# transponder-10_0_1.net
KiCad netlist of a schematic drawn in EAGLE
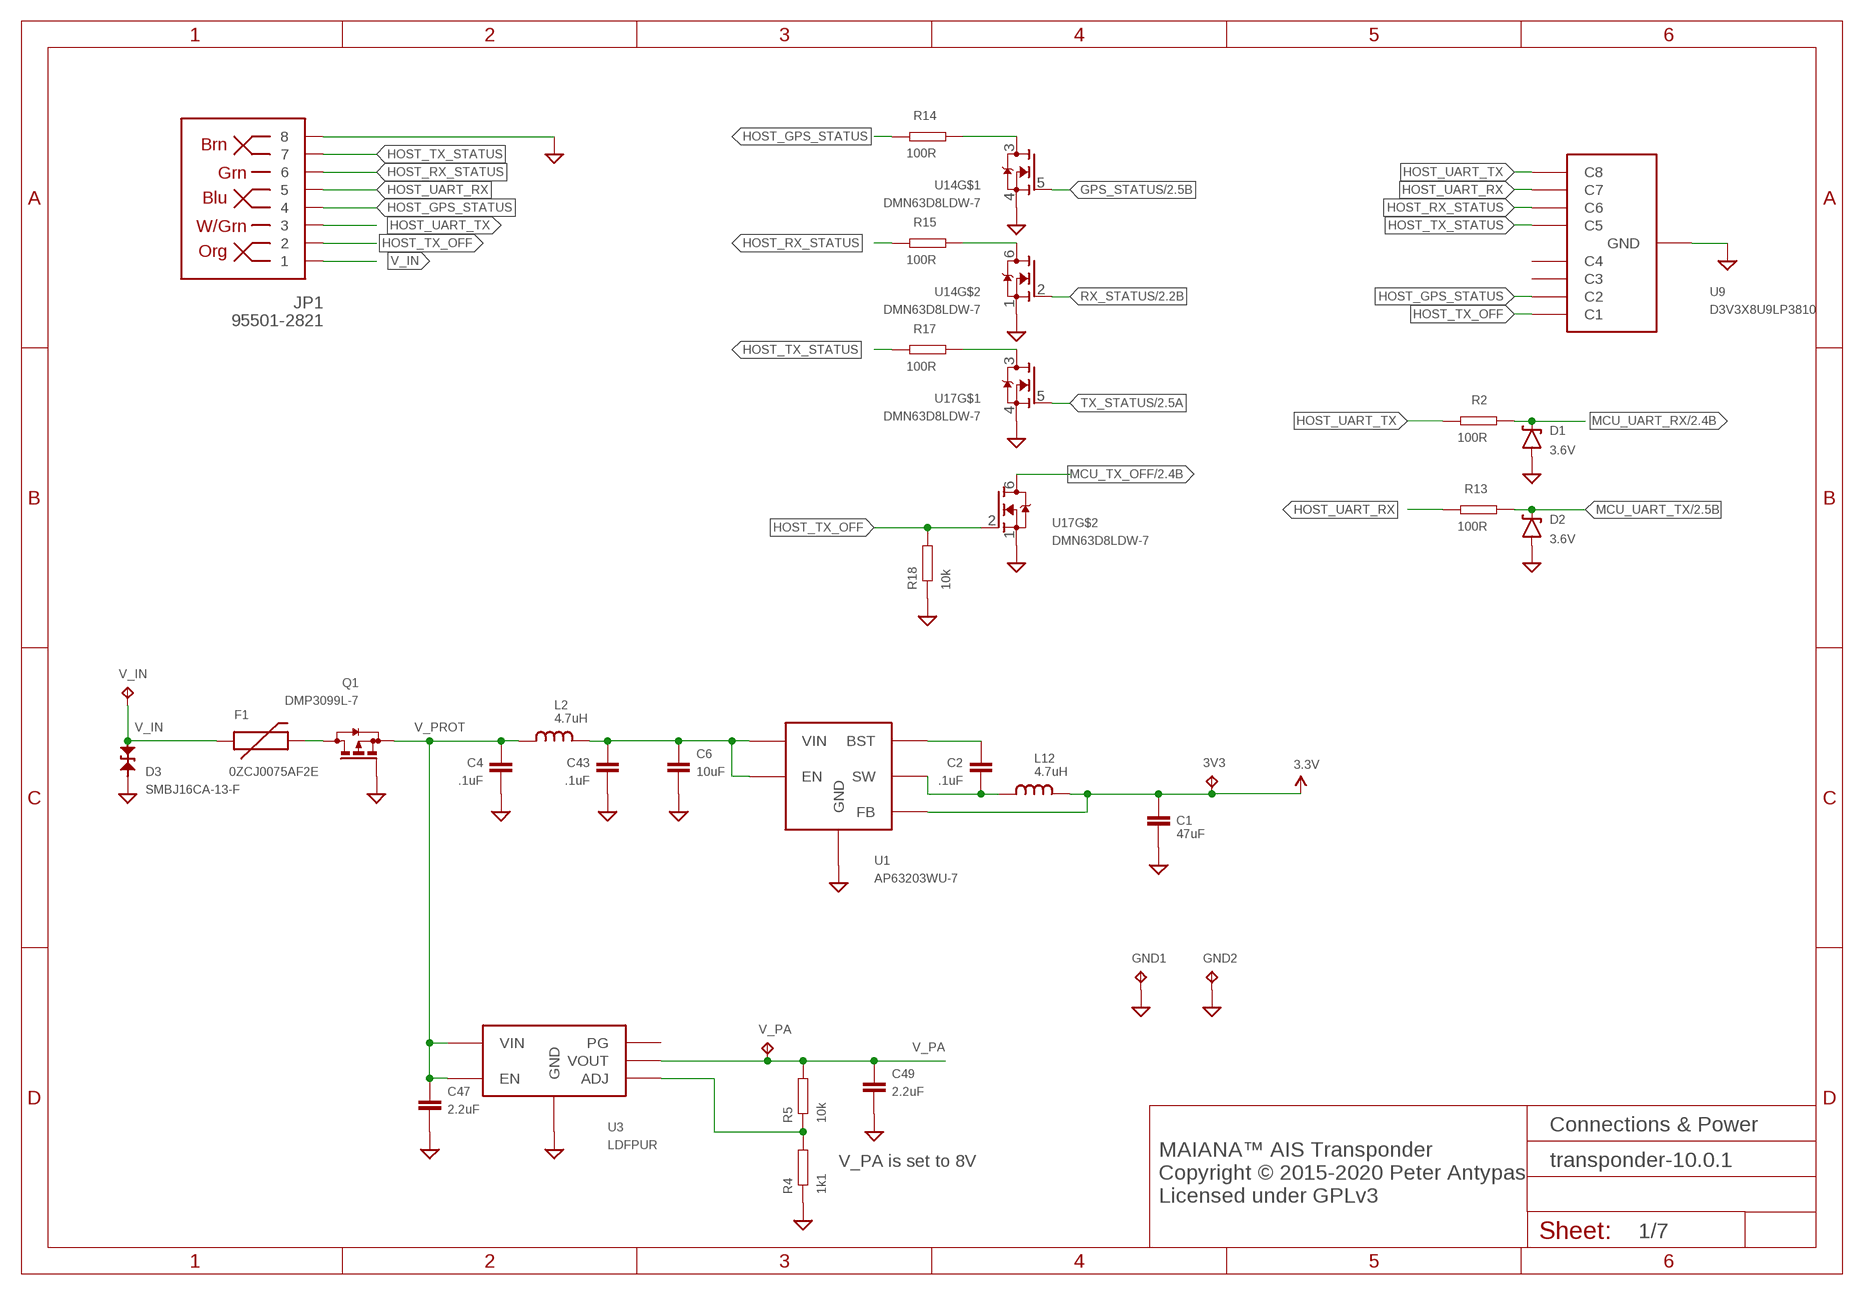
[diagram p0: schematic, sheet 1]
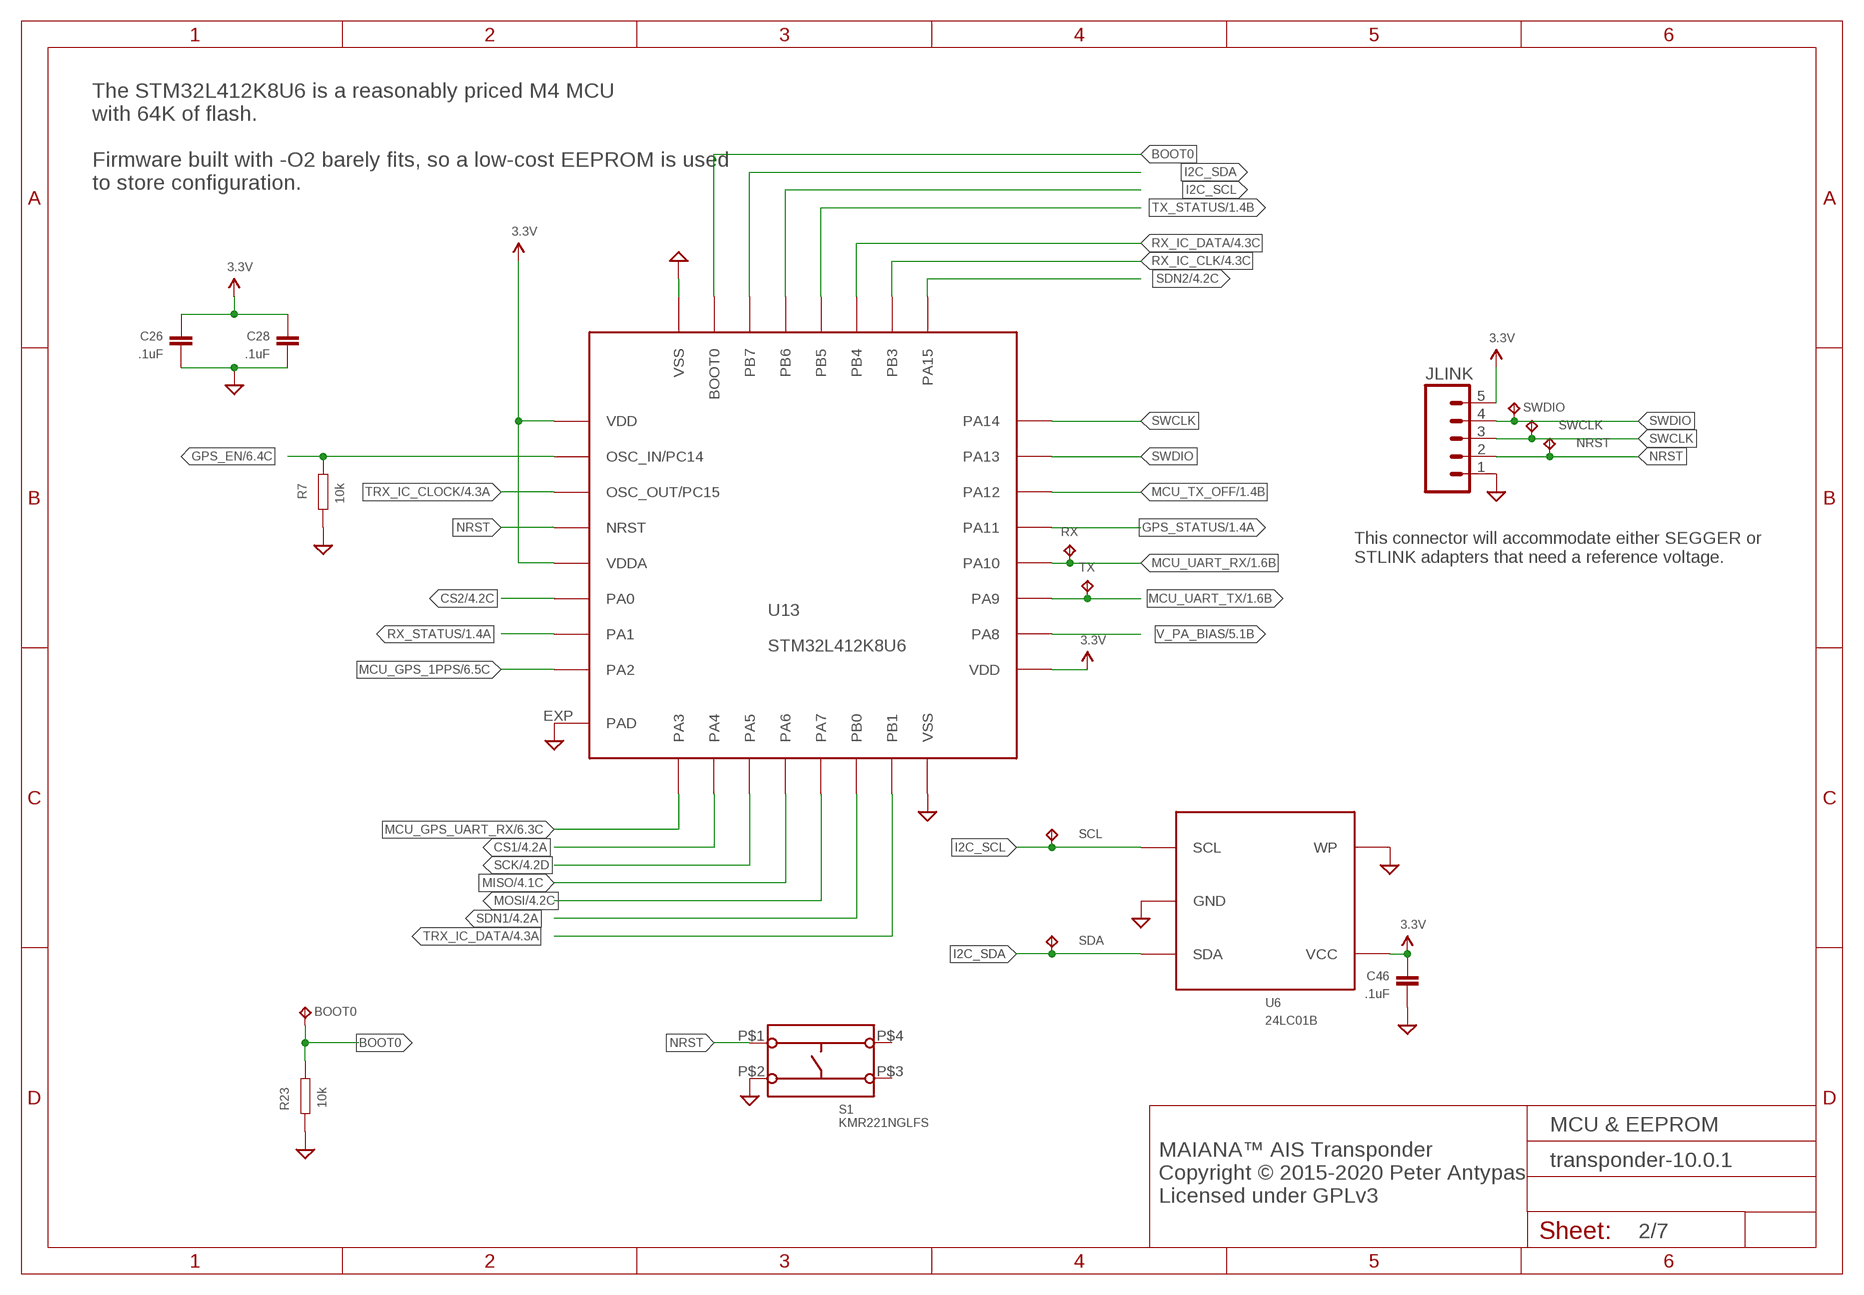
[diagram p1: schematic, sheet 2]
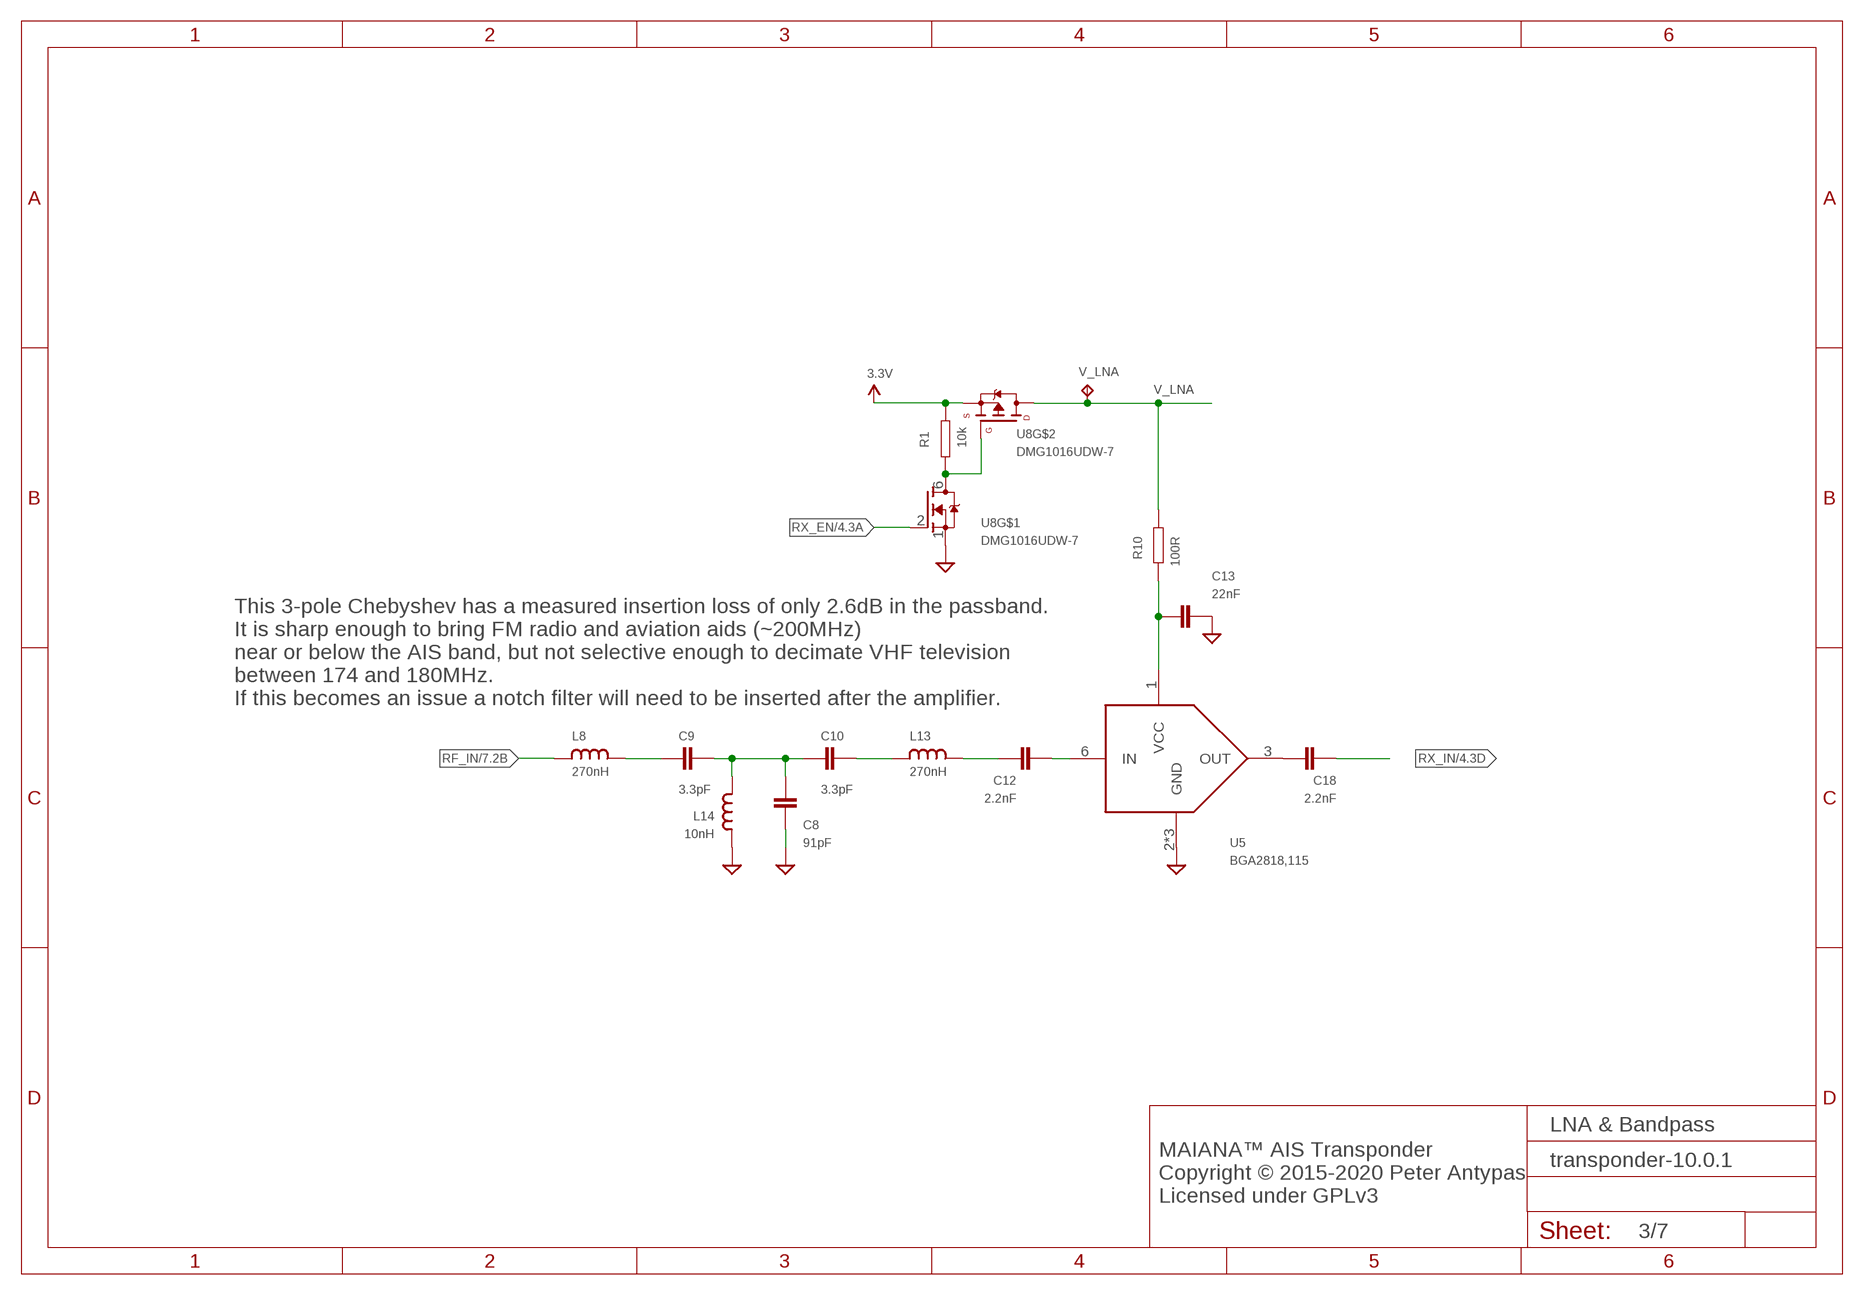
[diagram p2: schematic, sheet 3]
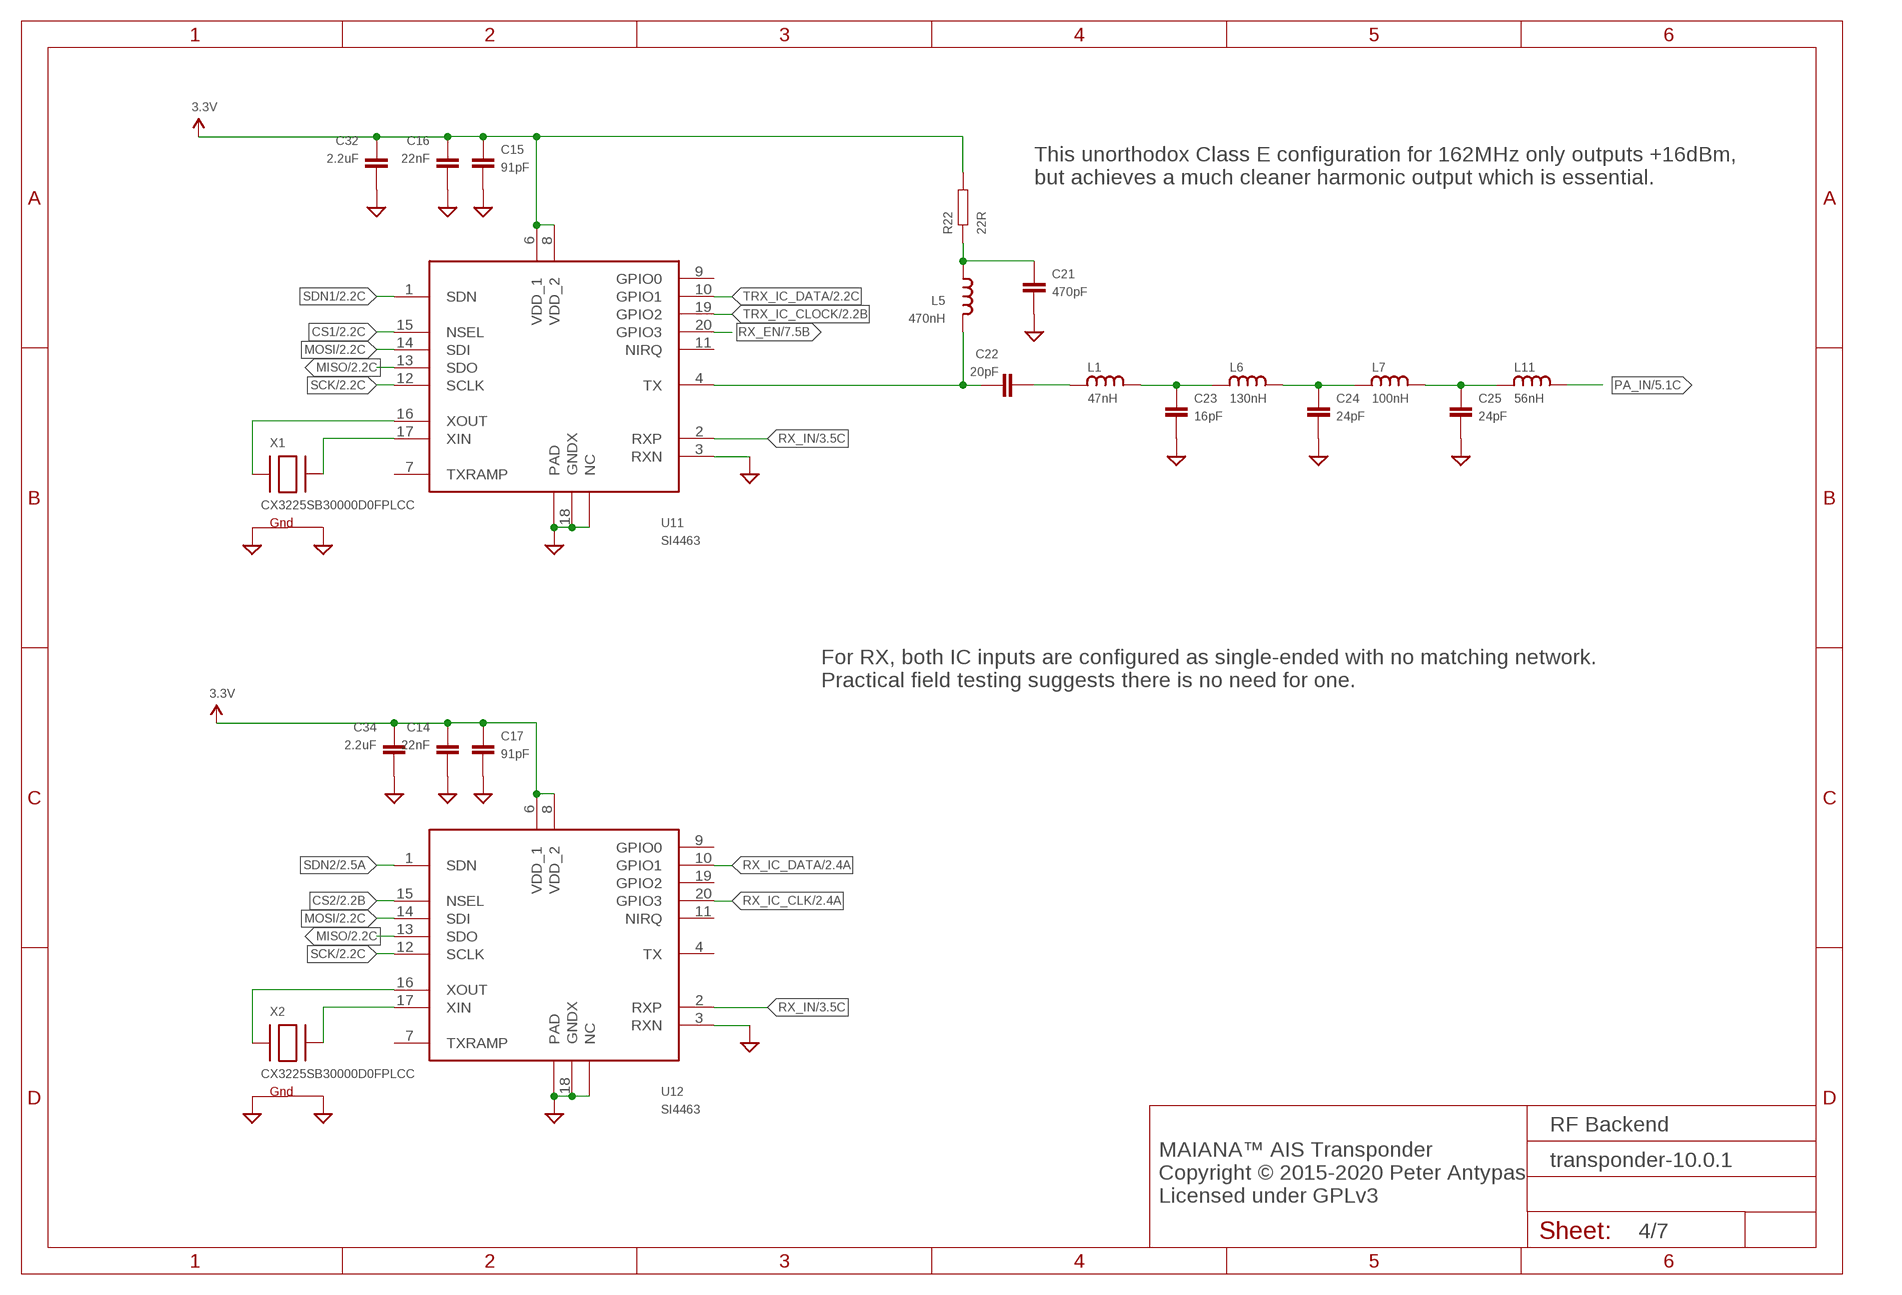
[diagram p3: schematic, sheet 4]
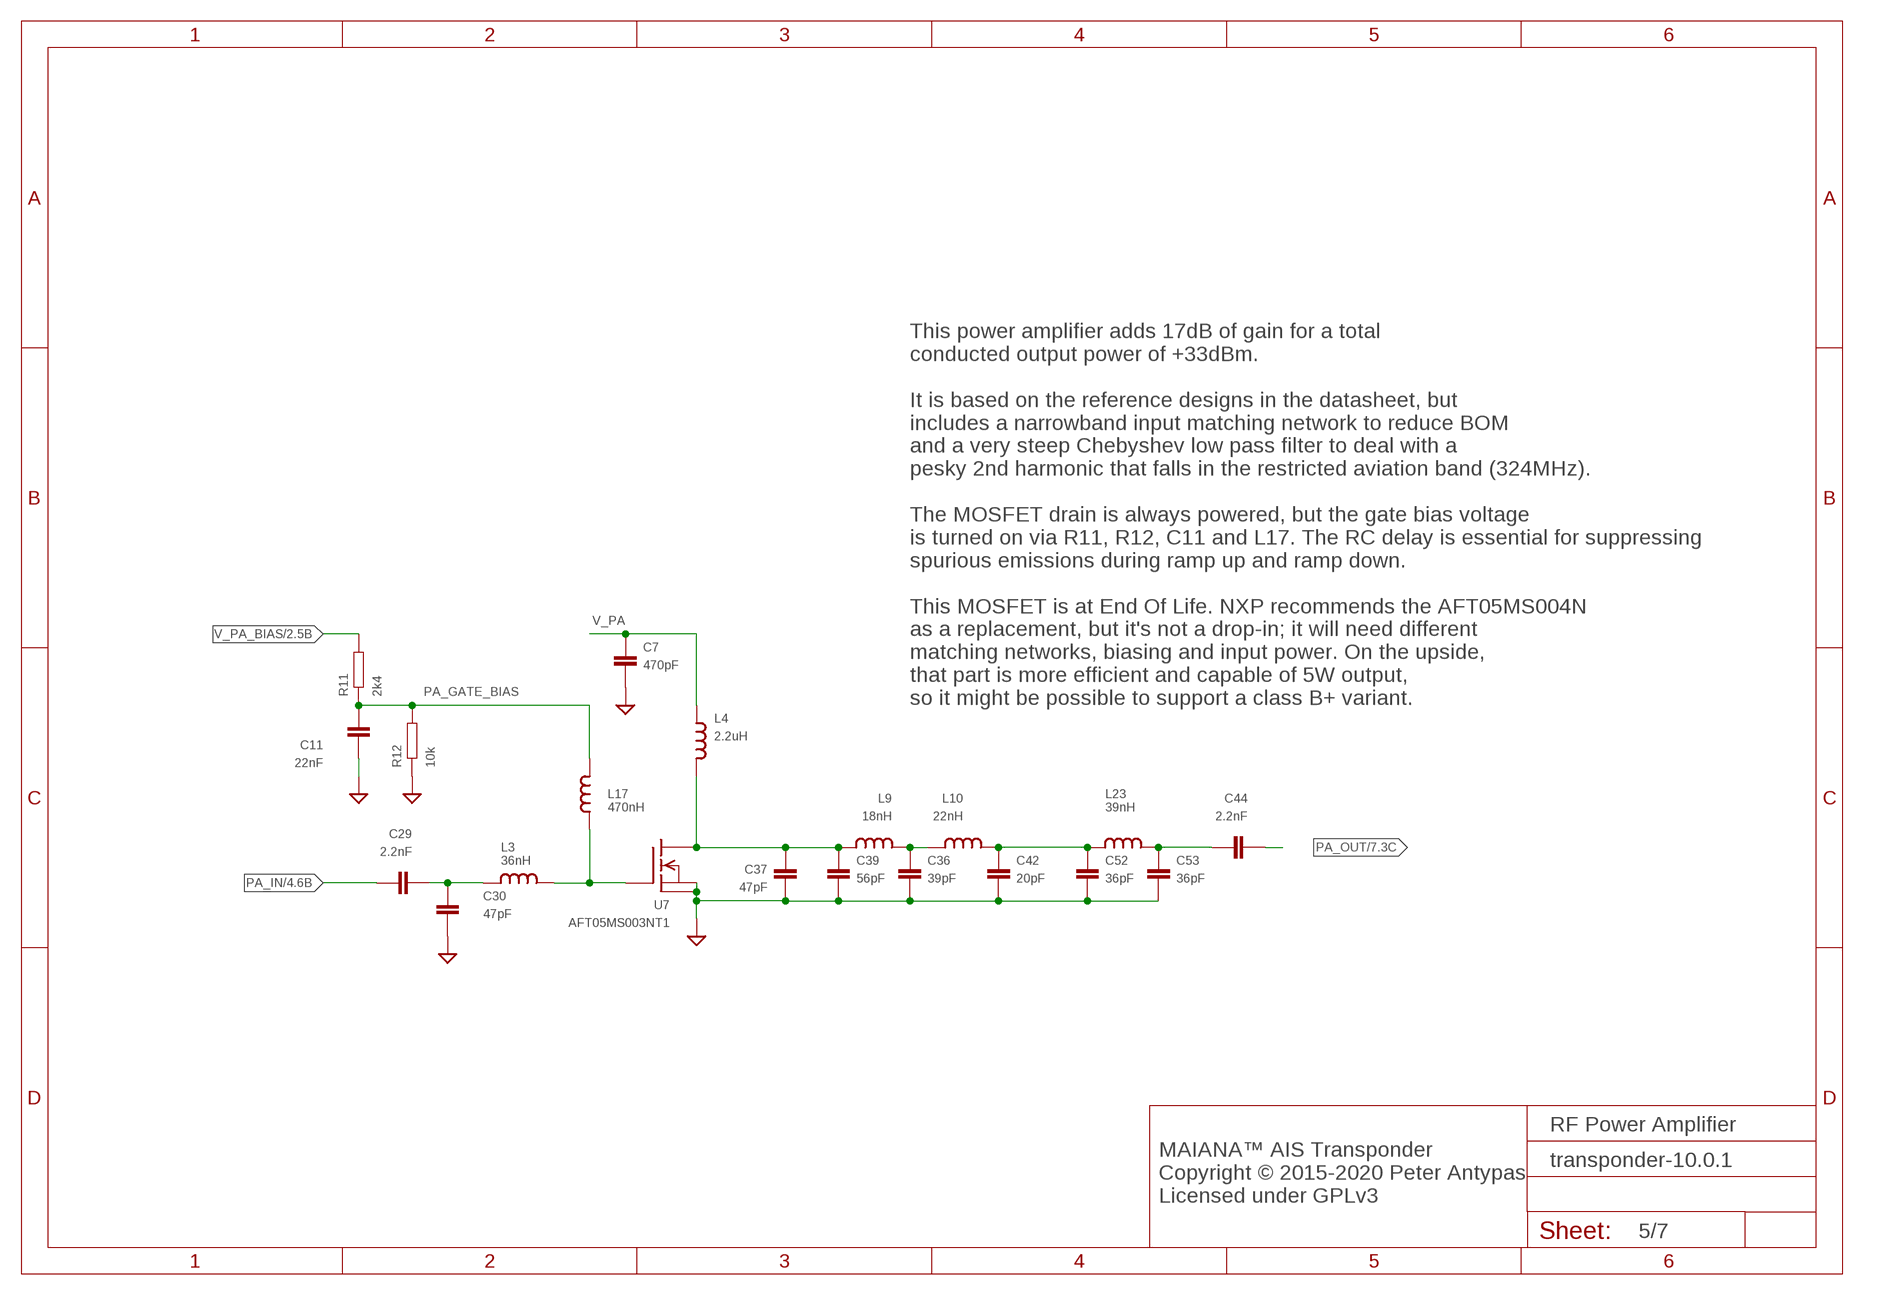
[diagram p4: schematic, sheet 5]
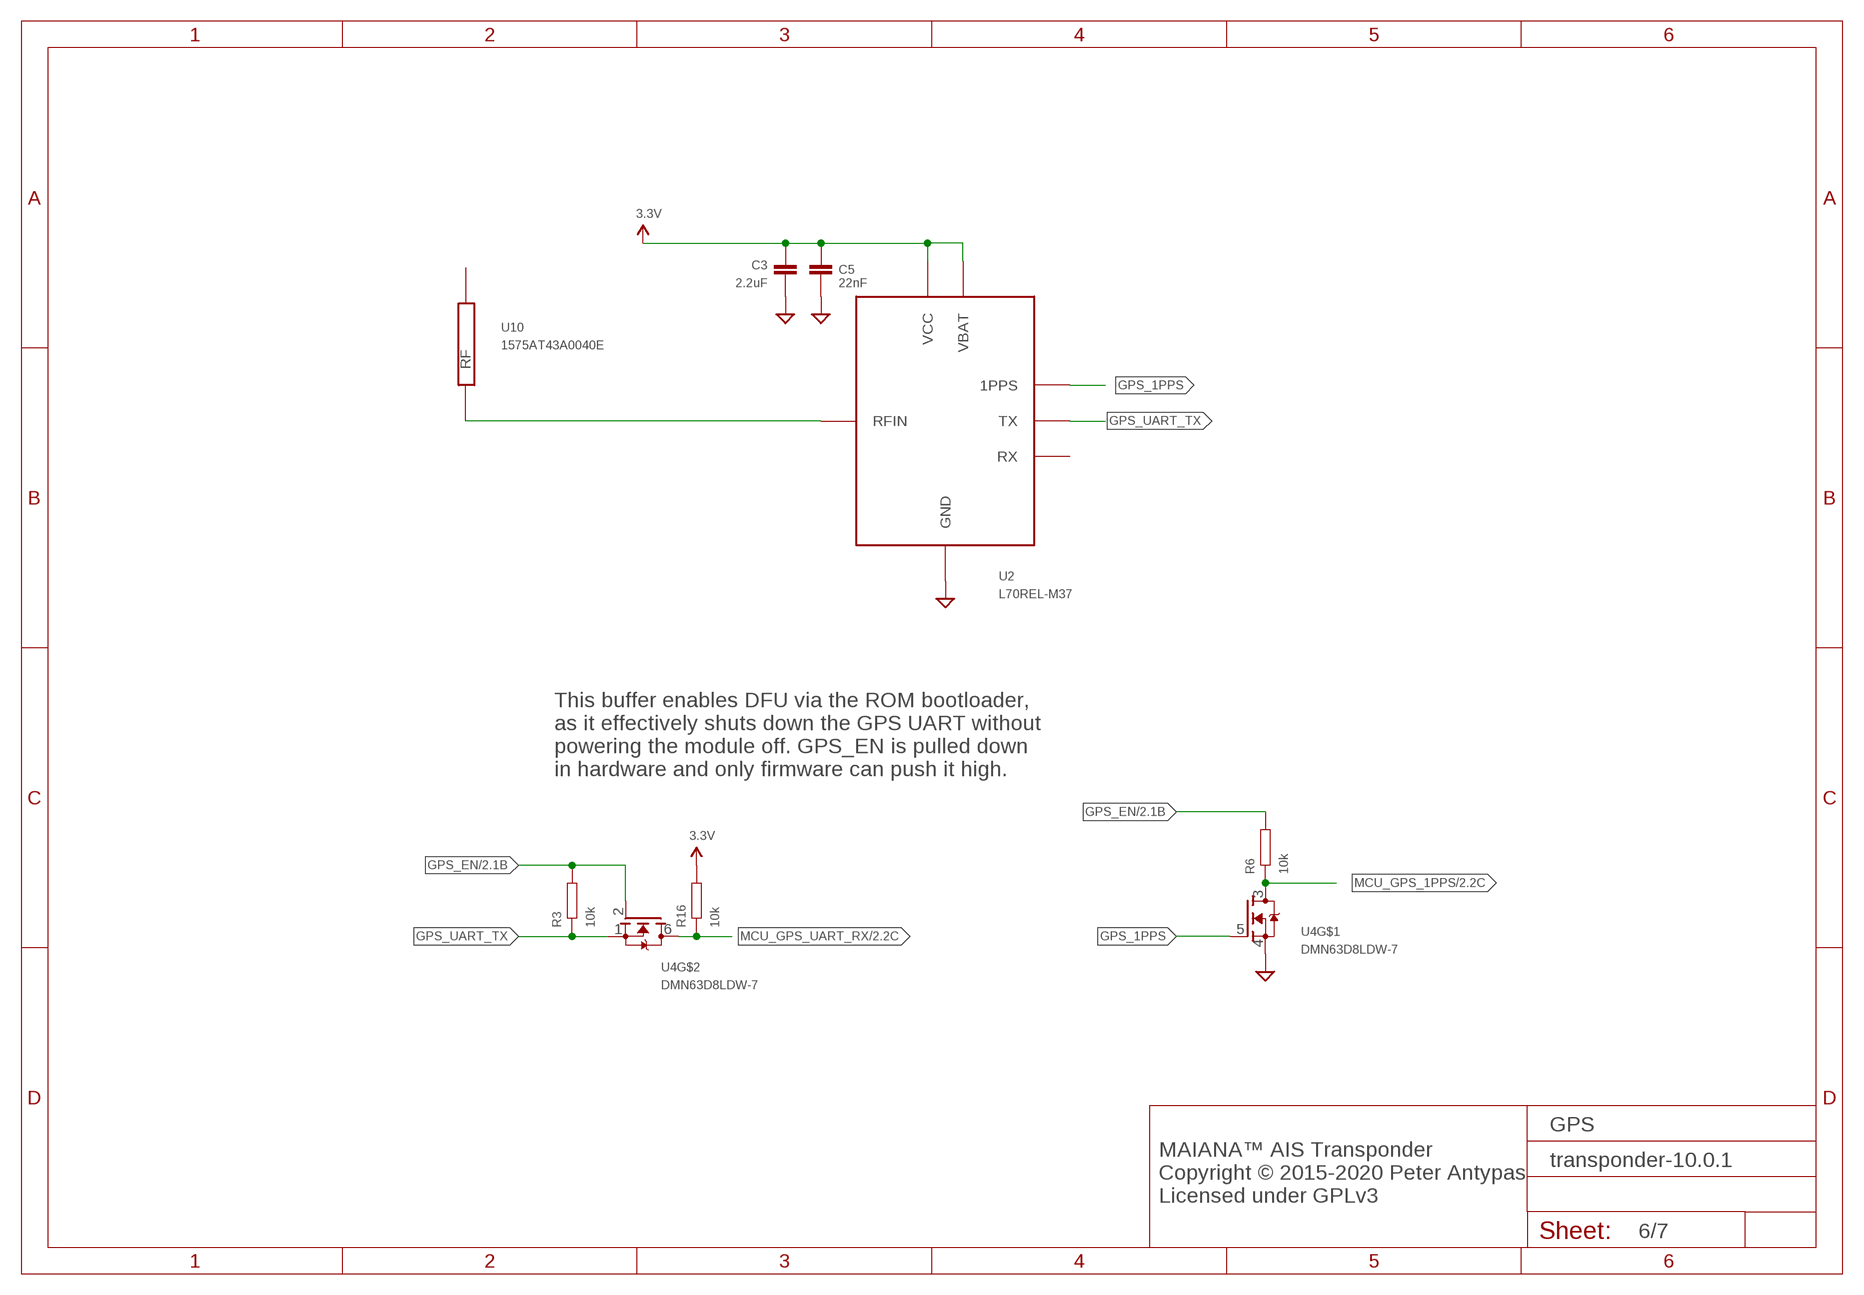
[diagram p5: schematic, sheet 6]
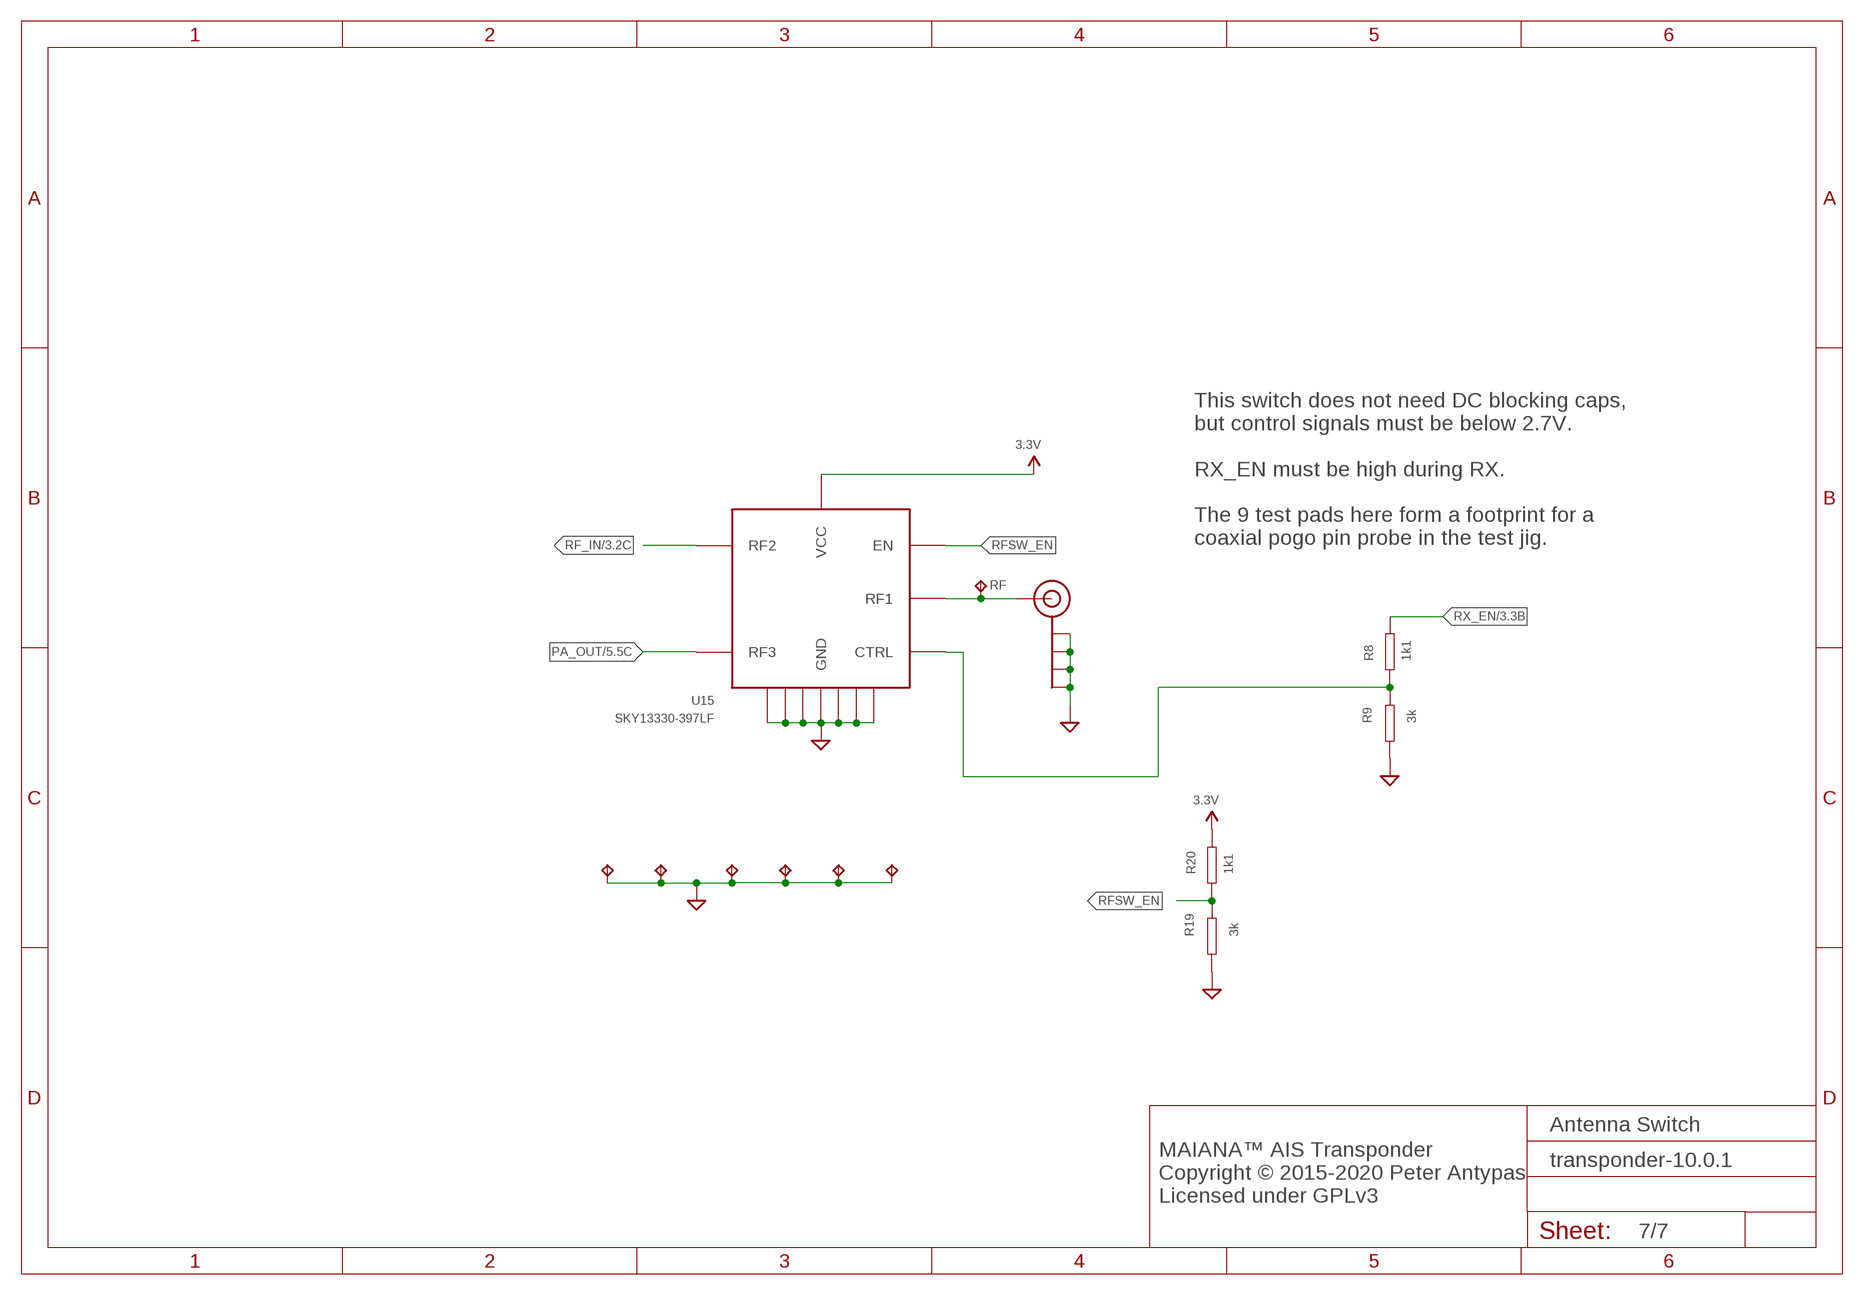
[diagram p6: schematic, sheet 7]

(export (version "E")
  (design (tool "Eeschema 10.0.6"))
  (components
    (comp (ref "C14")
      (value "22nF")
      (footprint "eagle-import:0603")
      (fields (field (name "PARTNO") "GRM188R71E223KA01D"))
      (libsource (lib "eagle-import") (part "CAPACITOR0603"))
    )
    (comp (ref "C15")
      (value "91pF")
      (footprint "eagle-import:0603")
      (fields (field (name "PARTNO") "GRM1885C2A910JA01D"))
      (libsource (lib "eagle-import") (part "CAPACITOR0603"))
    )
    (comp (ref "C16")
      (value "22nF")
      (footprint "eagle-import:0603")
      (fields (field (name "PARTNO") "GRM188R71E223KA01D"))
      (libsource (lib "eagle-import") (part "CAPACITOR0603"))
    )
    (comp (ref "C17")
      (value "91pF")
      (footprint "eagle-import:0603")
      (fields (field (name "PARTNO") "GRM1885C2A910JA01D"))
      (libsource (lib "eagle-import") (part "CAPACITOR0603"))
    )
    (comp (ref "C21")
      (value "470pF")
      (footprint "eagle-import:0603")
      (fields (field (name "PARTNO") "GRM1885C1H471JA01D"))
      (libsource (lib "eagle-import") (part "CAPACITOR0603"))
    )
    (comp (ref "C22")
      (value "20pF")
      (footprint "eagle-import:0603")
      (fields (field (name "PARTNO") "GRM1885C1H200JA01D"))
      (libsource (lib "eagle-import") (part "CAPACITOR0603"))
    )
    (comp (ref "C23")
      (value "16pF")
      (footprint "eagle-import:0603")
      (fields (field (name "PARTNO") "GCM1885C2A160JA16D"))
      (libsource (lib "eagle-import") (part "CAPACITOR0603"))
    )
    (comp (ref "C24")
      (value "24pF")
      (footprint "eagle-import:0603")
      (fields (field (name "PARTNO") "GRM1885C2A240JA01D"))
      (libsource (lib "eagle-import") (part "CAPACITOR0603"))
    )
    (comp (ref "C25")
      (value "24pF")
      (footprint "eagle-import:0603")
      (fields (field (name "PARTNO") "GRM1885C2A240JA01D"))
      (libsource (lib "eagle-import") (part "CAPACITOR0603"))
    )
    (comp (ref "C32")
      (value "2.2uF")
      (footprint "eagle-import:0603")
      (fields (field (name "PARTNO") "EMK107BJ225KA-T"))
      (libsource (lib "eagle-import") (part "CAPACITOR0603"))
    )
    (comp (ref "C34")
      (value "2.2uF")
      (footprint "eagle-import:0603")
      (fields (field (name "PARTNO") "EMK107BJ225KA-T"))
      (libsource (lib "eagle-import") (part "CAPACITOR0603"))
    )
    (comp (ref "L1")
      (value "47nH")
      (footprint "eagle-import:0603")
      (fields (field (name "PARTNO") "LQW18AN47NG00D"))
      (libsource (lib "eagle-import") (part "INDUCTOR0603"))
    )
    (comp (ref "L5")
      (value "470nH")
      (footprint "eagle-import:0603")
      (fields (field (name "PARTNO") "HK1608R47J-T"))
      (libsource (lib "eagle-import") (part "INDUCTOR0603"))
    )
    (comp (ref "L6")
      (value "130nH")
      (footprint "eagle-import:0603")
      (fields (field (name "PARTNO") "LQW18ANR13J00D"))
      (libsource (lib "eagle-import") (part "INDUCTOR0603"))
    )
    (comp (ref "L7")
      (value "100nH")
      (footprint "eagle-import:0603")
      (fields (field (name "PARTNO") "LQW18ANR10G00D"))
      (libsource (lib "eagle-import") (part "INDUCTOR0603"))
    )
    (comp (ref "L11")
      (value "56nH")
      (footprint "eagle-import:0603")
      (fields (field (name "PARTNO") "LQW18AN56NG00D"))
      (libsource (lib "eagle-import") (part "INDUCTOR0603"))
    )
    (comp (ref "R22")
      (value "22R")
      (footprint "eagle-import:0603")
      (fields (field (name "PARTNO") "RC0603JR-0722RL"))
      (libsource (lib "eagle-import") (part "RESISTOR0603"))
    )
    (comp (ref "U11")
      (value "SI4463")
      (footprint "eagle-import:SI4463")
      (fields (field (name "PARTNO") "SI4463-C2A-GMR"))
      (libsource (lib "eagle-import") (part "SI4463"))
    )
    (comp (ref "U12")
      (value "SI4463")
      (footprint "eagle-import:SI4463")
      (fields (field (name "PARTNO") "SI4463-C2A-GMR"))
      (libsource (lib "eagle-import") (part "SI4463"))
    )
    (comp (ref "X1")
      (value "CX3225SB30000D0FPLCC")
      (footprint "eagle-import:NX3225")
      (libsource (lib "eagle-import") (part "XTAL-4-3225"))
    )
    (comp (ref "X2")
      (value "CX3225SB30000D0FPLCC")
      (footprint "eagle-import:NX3225")
      (libsource (lib "eagle-import") (part "XTAL-4-3225"))
    )
    (comp (ref "C7")
      (value "470pF")
      (footprint "eagle-import:0603")
      (fields (field (name "PARTNO") "GRM1885C1H471JA01D"))
      (libsource (lib "eagle-import") (part "CAPACITOR0603"))
    )
    (comp (ref "C11")
      (value "22nF")
      (footprint "eagle-import:0603")
      (fields (field (name "PARTNO") "GRM188R71E223KA01D"))
      (libsource (lib "eagle-import") (part "CAPACITOR0603"))
    )
    (comp (ref "C29")
      (value "2.2nF")
      (footprint "eagle-import:0603")
      (fields (field (name "PARTNO") "GRM1885C1H222JA01J"))
      (libsource (lib "eagle-import") (part "CAPACITOR0603"))
    )
    (comp (ref "C30")
      (value "47pF")
      (footprint "eagle-import:0603")
      (fields (field (name "PARTNO") "GRM1885C1H470JA01J"))
      (libsource (lib "eagle-import") (part "CAPACITOR0603"))
    )
    (comp (ref "C36")
      (value "39pF")
      (footprint "eagle-import:0603")
      (fields (field (name "PARTNO") "GRM1885C1H390JA01D"))
      (libsource (lib "eagle-import") (part "CAPACITOR0603"))
    )
    (comp (ref "C37")
      (value "47pF")
      (footprint "eagle-import:0603")
      (fields (field (name "PARTNO") "GRM1885C1H470JA01J"))
      (libsource (lib "eagle-import") (part "CAPACITOR0603"))
    )
    (comp (ref "C39")
      (value "56pF")
      (footprint "eagle-import:0603")
      (fields (field (name "PARTNO") "GRM1885C1H560JA01D"))
      (libsource (lib "eagle-import") (part "CAPACITOR0603"))
    )
    (comp (ref "C42")
      (value "20pF")
      (footprint "eagle-import:0603")
      (fields (field (name "PARTNO") "GRM1885C1H200JA01D"))
      (libsource (lib "eagle-import") (part "CAPACITOR0603"))
    )
    (comp (ref "C44")
      (value "2.2nF")
      (footprint "eagle-import:0603")
      (fields (field (name "PARTNO") "GRM1885C1H222JA01J"))
      (libsource (lib "eagle-import") (part "CAPACITOR0603"))
    )
    (comp (ref "C52")
      (value "36pF")
      (footprint "eagle-import:0603")
      (fields (field (name "PARTNO") "06035A360JAT2A"))
      (libsource (lib "eagle-import") (part "CAPACITOR0603"))
    )
    (comp (ref "C53")
      (value "36pF")
      (footprint "eagle-import:0603")
      (fields (field (name "PARTNO") "06035A360JAT2A"))
      (libsource (lib "eagle-import") (part "CAPACITOR0603"))
    )
    (comp (ref "L3")
      (value "36nH")
      (footprint "eagle-import:0603")
      (fields (field (name "PARTNO") "LQW18AN36NG00D"))
      (libsource (lib "eagle-import") (part "INDUCTOR0603"))
    )
    (comp (ref "L4")
      (value "2.2uH")
      (footprint "eagle-import:0805")
      (fields (field (name "PARTNO") "BRC2012T2R2MD"))
      (libsource (lib "eagle-import") (part "INDUCTOR0805"))
    )
    (comp (ref "L9")
      (value "18nH")
      (footprint "eagle-import:0603")
      (fields (field (name "PARTNO") "LQW18AN18NG00D"))
      (libsource (lib "eagle-import") (part "INDUCTOR0603"))
    )
    (comp (ref "L10")
      (value "22nH")
      (footprint "eagle-import:0603")
      (fields (field (name "PARTNO") "LQW18AN22NJ00D"))
      (libsource (lib "eagle-import") (part "INDUCTOR0603"))
    )
    (comp (ref "L17")
      (value "470nH")
      (footprint "eagle-import:1206")
      (fields (field (name "PARTNO") "HK1608R47J-T"))
      (libsource (lib "eagle-import") (part "INDUCTOR1206"))
    )
    (comp (ref "L23")
      (value "39nH")
      (footprint "eagle-import:0603")
      (fields (field (name "PARTNO") "LQW18AN39NG00D"))
      (libsource (lib "eagle-import") (part "INDUCTOR0603"))
    )
    (comp (ref "R11")
      (value "2k4")
      (footprint "eagle-import:0603")
      (fields (field (name "PARTNO") "RC0603JR-072K4L"))
      (libsource (lib "eagle-import") (part "RESISTOR0603"))
    )
    (comp (ref "R12")
      (value "10k")
      (footprint "eagle-import:0603")
      (fields (field (name "PARTNO") "RC0603JR-0710KL"))
      (libsource (lib "eagle-import") (part "RESISTOR0603"))
    )
    (comp (ref "U7")
      (value "AFT05MS003NT1")
      (footprint "eagle-import:SOT-89")
      (libsource (lib "eagle-import") (part "AFT0SMS003N"))
    )
    (comp (ref "C8")
      (value "91pF")
      (footprint "eagle-import:0603")
      (fields (field (name "PARTNO") "GRM1885C2A910JA01D"))
      (libsource (lib "eagle-import") (part "CAPACITOR0603"))
    )
    (comp (ref "C9")
      (value "3.3pF")
      (footprint "eagle-import:0603")
      (fields (field (name "PARTNO") "GRM1885C1H3R3BA01D"))
      (libsource (lib "eagle-import") (part "CAPACITOR0603"))
    )
    (comp (ref "C10")
      (value "3.3pF")
      (footprint "eagle-import:0603")
      (fields (field (name "PARTNO") "GRM1885C1H3R3BA01D"))
      (libsource (lib "eagle-import") (part "CAPACITOR0603"))
    )
    (comp (ref "C12")
      (value "2.2nF")
      (footprint "eagle-import:0603")
      (fields (field (name "PARTNO") "GRM1885C1H222JA01J"))
      (libsource (lib "eagle-import") (part "CAPACITOR0603"))
    )
    (comp (ref "C13")
      (value "22nF")
      (footprint "eagle-import:0603")
      (fields (field (name "PARTNO") "GRM188R71E223KA01D"))
      (libsource (lib "eagle-import") (part "CAPACITOR0603"))
    )
    (comp (ref "C18")
      (value "2.2nF")
      (footprint "eagle-import:0603")
      (fields (field (name "PARTNO") "GRM1885C1H222JA01J"))
      (libsource (lib "eagle-import") (part "CAPACITOR0603"))
    )
    (comp (ref "L8")
      (value "270nH")
      (footprint "eagle-import:0603")
      (fields (field (name "PARTNO") "LQW18ANR27J00D"))
      (libsource (lib "eagle-import") (part "INDUCTOR0603"))
    )
    (comp (ref "L13")
      (value "270nH")
      (footprint "eagle-import:0603")
      (fields (field (name "PARTNO") "LQW18ANR27J00D"))
      (libsource (lib "eagle-import") (part "INDUCTOR0603"))
    )
    (comp (ref "L14")
      (value "10nH")
      (footprint "eagle-import:0603")
      (fields (field (name "PARTNO") "LQW18AN10NG00D"))
      (libsource (lib "eagle-import") (part "INDUCTOR0603"))
    )
    (comp (ref "R1")
      (value "10k")
      (footprint "eagle-import:0603")
      (fields (field (name "PARTNO") "RC0603JR-0710KL"))
      (libsource (lib "eagle-import") (part "RESISTOR0603"))
    )
    (comp (ref "R10")
      (value "100R")
      (footprint "eagle-import:0603")
      (fields (field (name "PARTNO") "RC0603JR-07100RL"))
      (libsource (lib "eagle-import") (part "RESISTOR0603"))
    )
    (comp (ref "U5")
      (value "BGA2818,115")
      (footprint "eagle-import:SOT363")
      (libsource (lib "eagle-import") (part "BGA2870"))
    )
    (comp (ref "U8")
      (value "DMG1016UDW-7")
      (footprint "eagle-import:SOT363")
      (libsource (lib "eagle-import") (part "DMG1016UDW"))
    )
    (comp (ref "V_LNA")
      (value "TPTP12R")
      (footprint "eagle-import:TP12R")
      (libsource (lib "eagle-import") (part "TPTP12R"))
    )
    (comp (ref "C3")
      (value "2.2uF")
      (footprint "eagle-import:0603")
      (fields (field (name "PARTNO") "EMK107BJ225KA-T"))
      (libsource (lib "eagle-import") (part "CAPACITOR0603"))
    )
    (comp (ref "C5")
      (value "22nF")
      (footprint "eagle-import:0603")
      (fields (field (name "PARTNO") "GRM188R71E223KA01D"))
      (libsource (lib "eagle-import") (part "CAPACITOR0603"))
    )
    (comp (ref "R3")
      (value "10k")
      (footprint "eagle-import:0603")
      (fields (field (name "PARTNO") "RC0603JR-0710KL"))
      (libsource (lib "eagle-import") (part "RESISTOR0603"))
    )
    (comp (ref "R6")
      (value "10k")
      (footprint "eagle-import:0603")
      (fields (field (name "PARTNO") "RC0603JR-0710KL"))
      (libsource (lib "eagle-import") (part "RESISTOR0603"))
    )
    (comp (ref "R16")
      (value "10k")
      (footprint "eagle-import:0603")
      (fields (field (name "PARTNO") "RC0603JR-0710KL"))
      (libsource (lib "eagle-import") (part "RESISTOR0603"))
    )
    (comp (ref "U2")
      (value "L70REL-M37")
      (footprint "eagle-import:GPS_MODULE")
      (fields (field (name "PARTNO") "L70B-M39"))
      (libsource (lib "eagle-import") (part "L70"))
    )
    (comp (ref "U4")
      (value "DMN63D8LDW-7")
      (footprint "eagle-import:SOT363")
      (fields (field (name "PARTNO") "DMN63D8LDW-7"))
      (libsource (lib "eagle-import") (part "DMN63D8LDW"))
    )
    (comp (ref "U10")
      (value "1575AT43A0040E")
      (footprint "eagle-import:1575AT43A0040E")
      (libsource (lib "eagle-import") (part "1575AT43A0040E"))
    )
    (comp (ref "3V3")
      (value "TPTP12R")
      (footprint "eagle-import:TP12R")
      (libsource (lib "eagle-import") (part "TPTP12R"))
    )
    (comp (ref "C1")
      (value "47uF")
      (footprint "eagle-import:1206")
      (fields (field (name "PARTNO") "CL31A476MQHNNNE"))
      (libsource (lib "eagle-import") (part "CAPACITOR1206"))
    )
    (comp (ref "C2")
      (value ".1uF")
      (footprint "eagle-import:0603")
      (fields (field (name "PARTNO") "EMK107B7104KAHT"))
      (libsource (lib "eagle-import") (part "CAPACITOR0603"))
    )
    (comp (ref "C4")
      (value ".1uF")
      (footprint "eagle-import:0603")
      (fields (field (name "PARTNO") "EMK107B7104KAHT"))
      (libsource (lib "eagle-import") (part "CAPACITOR0603"))
    )
    (comp (ref "C6")
      (value "10uF")
      (footprint "eagle-import:0805")
      (fields (field (name "PARTNO") " EMK212ABJ106KG-T"))
      (libsource (lib "eagle-import") (part "CAPACITOR0805"))
    )
    (comp (ref "C43")
      (value ".1uF")
      (footprint "eagle-import:0603")
      (fields (field (name "PARTNO") "EMK107B7104KAHT"))
      (libsource (lib "eagle-import") (part "CAPACITOR0603"))
    )
    (comp (ref "C47")
      (value "2.2uF")
      (footprint "eagle-import:0603")
      (fields (field (name "PARTNO") "EMK107BJ225KA-T"))
      (libsource (lib "eagle-import") (part "CAPACITOR0603"))
    )
    (comp (ref "C49")
      (value "2.2uF")
      (footprint "eagle-import:0603")
      (fields (field (name "PARTNO") "EMK107BJ225KA-T"))
      (libsource (lib "eagle-import") (part "CAPACITOR0603"))
    )
    (comp (ref "D1")
      (value "3.6V")
      (footprint "eagle-import:SOD-323")
      (fields (field (name "PARTNO") "MM3Z3V6C"))
      (libsource (lib "eagle-import") (part "DIODE-ZENER3.3V"))
    )
    (comp (ref "D2")
      (value "3.6V")
      (footprint "eagle-import:SOD-323")
      (fields (field (name "PARTNO") "MM3Z3V6C"))
      (libsource (lib "eagle-import") (part "DIODE-ZENER3.3V"))
    )
    (comp (ref "D3")
      (value "SMBJ16CA-13-F")
      (footprint "eagle-import:SMB-BIDIR")
      (fields (field (name "PARTNO") "SMBJ16CA-13-F"))
      (libsource (lib "eagle-import") (part "DIODE-TVS-BIDIRSMB"))
    )
    (comp (ref "F1")
      (value "0ZCJ0075AF2E")
      (footprint "eagle-import:PTC-1206")
      (libsource (lib "eagle-import") (part "PTCSMD"))
    )
    (comp (ref "GND1")
      (value "TPTP12R")
      (footprint "eagle-import:TP12R")
      (libsource (lib "eagle-import") (part "TPTP12R"))
    )
    (comp (ref "GND2")
      (value "TPTP12R")
      (footprint "eagle-import:TP12R")
      (libsource (lib "eagle-import") (part "TPTP12R"))
    )
    (comp (ref "JP1")
      (value "95501-2821")
      (footprint "eagle-import:RJ45-8")
      (libsource (lib "eagle-import") (part "RJ45-8PTH"))
    )
    (comp (ref "L2")
      (value "4.7uH")
      (footprint "eagle-import:0805")
      (fields (field (name "PARTNO") "MLZ2012M4R7WT000"))
      (libsource (lib "eagle-import") (part "INDUCTOR0805"))
    )
    (comp (ref "L12")
      (value "4.7uH")
      (footprint "eagle-import:0805")
      (fields (field (name "PARTNO") "MLZ2012M4R7WT000"))
      (libsource (lib "eagle-import") (part "INDUCTOR0805"))
    )
    (comp (ref "Q1")
      (value "DMP3099L-7")
      (footprint "eagle-import:SOT23")
      (libsource (lib "eagle-import") (part "BSS84"))
    )
    (comp (ref "R2")
      (value "100R")
      (footprint "eagle-import:0603")
      (fields (field (name "PARTNO") "RC0603JR-07100RL"))
      (libsource (lib "eagle-import") (part "RESISTOR0603"))
    )
    (comp (ref "R4")
      (value "1k1")
      (footprint "eagle-import:0603")
      (fields (field (name "PARTNO") "RC0603JR-071K1L"))
      (libsource (lib "eagle-import") (part "RESISTOR0603"))
    )
    (comp (ref "R5")
      (value "10k")
      (footprint "eagle-import:0603")
      (fields (field (name "PARTNO") "RC0603JR-0710KL"))
      (libsource (lib "eagle-import") (part "RESISTOR0603"))
    )
    (comp (ref "R13")
      (value "100R")
      (footprint "eagle-import:0603")
      (fields (field (name "PARTNO") "RC0603JR-07100RL"))
      (libsource (lib "eagle-import") (part "RESISTOR0603"))
    )
    (comp (ref "R14")
      (value "100R")
      (footprint "eagle-import:0603")
      (fields (field (name "PARTNO") "RC0603JR-07100RL"))
      (libsource (lib "eagle-import") (part "RESISTOR0603"))
    )
    (comp (ref "R15")
      (value "100R")
      (footprint "eagle-import:0603")
      (fields (field (name "PARTNO") "RC0603JR-07100RL"))
      (libsource (lib "eagle-import") (part "RESISTOR0603"))
    )
    (comp (ref "R17")
      (value "100R")
      (footprint "eagle-import:0603")
      (fields (field (name "PARTNO") "RC0603JR-07100RL"))
      (libsource (lib "eagle-import") (part "RESISTOR0603"))
    )
    (comp (ref "R18")
      (value "10k")
      (footprint "eagle-import:0603")
      (fields (field (name "PARTNO") "RC0603JR-0710KL"))
      (libsource (lib "eagle-import") (part "RESISTOR0603"))
    )
    (comp (ref "U1")
      (value "AP63203WU-7")
      (footprint "eagle-import:SOT23-6")
      (libsource (lib "eagle-import") (part "AP63203"))
    )
    (comp (ref "U3")
      (value "LDFPUR")
      (footprint "eagle-import:DFN-6")
      (libsource (lib "eagle-import") (part "LDF"))
    )
    (comp (ref "U9")
      (value "D3V3X8U9LP3810")
      (footprint "eagle-import:U-DFN3810-9(B)")
      (libsource (lib "eagle-import") (part "D3V3X8U9LP3810"))
    )
    (comp (ref "U14")
      (value "DMN63D8LDW-7")
      (footprint "eagle-import:SOT363")
      (fields (field (name "PARTNO") "DMN63D8LDW-7"))
      (libsource (lib "eagle-import") (part "DMN63D8LDW"))
    )
    (comp (ref "U17")
      (value "DMN63D8LDW-7")
      (footprint "eagle-import:SOT363")
      (fields (field (name "PARTNO") "DMN63D8LDW-7"))
      (libsource (lib "eagle-import") (part "DMN63D8LDW"))
    )
    (comp (ref "V_IN")
      (value "TPTP12R")
      (footprint "eagle-import:TP12R")
      (libsource (lib "eagle-import") (part "TPTP12R"))
    )
    (comp (ref "V_PA")
      (value "TPTP12R")
      (footprint "eagle-import:TP12R")
      (libsource (lib "eagle-import") (part "TPTP12R"))
    )
    (comp (ref "BOOT0")
      (value "TPTP12R")
      (footprint "eagle-import:TP12R")
      (libsource (lib "eagle-import") (part "TPTP12R"))
    )
    (comp (ref "C26")
      (value ".1uF")
      (footprint "eagle-import:0603")
      (fields (field (name "PARTNO") "EMK107B7104KAHT"))
      (libsource (lib "eagle-import") (part "CAPACITOR0603"))
    )
    (comp (ref "C28")
      (value ".1uF")
      (footprint "eagle-import:0603")
      (fields (field (name "PARTNO") "EMK107B7104KAHT"))
      (libsource (lib "eagle-import") (part "CAPACITOR0603"))
    )
    (comp (ref "C46")
      (value ".1uF")
      (footprint "eagle-import:0603")
      (fields (field (name "PARTNO") "EMK107B7104KAHT"))
      (libsource (lib "eagle-import") (part "CAPACITOR0603"))
    )
    (comp (ref "JLINK")
      (value "M05PTH")
      (footprint "eagle-import:1X05")
      (libsource (lib "eagle-import") (part "M05PTH"))
    )
    (comp (ref "NRST")
      (value "TPTP12R")
      (footprint "eagle-import:TP12R")
      (libsource (lib "eagle-import") (part "TPTP12R"))
    )
    (comp (ref "R7")
      (value "10k")
      (footprint "eagle-import:0603")
      (fields (field (name "PARTNO") "RC0603JR-0710KL"))
      (libsource (lib "eagle-import") (part "RESISTOR0603"))
    )
    (comp (ref "R23")
      (value "10k")
      (footprint "eagle-import:0603")
      (fields (field (name "PARTNO") "RC0603JR-0710KL"))
      (libsource (lib "eagle-import") (part "RESISTOR0603"))
    )
    (comp (ref "RX")
      (value "TPTP12R")
      (footprint "eagle-import:TP12R")
      (libsource (lib "eagle-import") (part "TPTP12R"))
    )
    (comp (ref "S1")
      (value "KMR221NGLFS")
      (footprint "eagle-import:KMR221NGLFS")
      (libsource (lib "eagle-import") (part "KMR221NGLFS"))
    )
    (comp (ref "SCL")
      (value "TPTP12R")
      (footprint "eagle-import:TP12R")
      (libsource (lib "eagle-import") (part "TPTP12R"))
    )
    (comp (ref "SDA")
      (value "TPTP12R")
      (footprint "eagle-import:TP12R")
      (libsource (lib "eagle-import") (part "TPTP12R"))
    )
    (comp (ref "SWCLK")
      (value "TPTP12R")
      (footprint "eagle-import:TP12R")
      (libsource (lib "eagle-import") (part "TPTP12R"))
    )
    (comp (ref "SWDIO")
      (value "TPTP12R")
      (footprint "eagle-import:TP12R")
      (libsource (lib "eagle-import") (part "TPTP12R"))
    )
    (comp (ref "TX")
      (value "TPTP12R")
      (footprint "eagle-import:TP12R")
      (libsource (lib "eagle-import") (part "TPTP12R"))
    )
    (comp (ref "U6")
      (value "24LC01B")
      (footprint "eagle-import:SOT23-5")
      (fields (field (name "PARTNO") "24LC01BT-I/OT"))
      (libsource (lib "eagle-import") (part "24LC01B"))
    )
    (comp (ref "U13")
      (value "STM32L412K8U6")
      (footprint "eagle-import:QFN32")
      (libsource (lib "eagle-import") (part "STM32L432KXXX"))
    )
    (comp (ref "J$1")
      (value "SMA_EDGE")
      (footprint "eagle-import:SMA-EDGE")
      (libsource (lib "eagle-import") (part "SMA_EDGE"))
    )
    (comp (ref "R8")
      (value "1k1")
      (footprint "eagle-import:0603")
      (fields (field (name "PARTNO") "RC0603JR-071K1L"))
      (libsource (lib "eagle-import") (part "RESISTOR0603"))
    )
    (comp (ref "R9")
      (value "3k")
      (footprint "eagle-import:0603")
      (fields (field (name "PARTNO") "RC0603JR-073KL"))
      (libsource (lib "eagle-import") (part "RESISTOR0603"))
    )
    (comp (ref "R19")
      (value "3k")
      (footprint "eagle-import:0603")
      (fields (field (name "PARTNO") "RC0603JR-073KL"))
      (libsource (lib "eagle-import") (part "RESISTOR0603"))
    )
    (comp (ref "R20")
      (value "1k1")
      (footprint "eagle-import:0603")
      (fields (field (name "PARTNO") "RC0603JR-071K1L"))
      (libsource (lib "eagle-import") (part "RESISTOR0603"))
    )
    (comp (ref "RF")
      (value "TPTP10R")
      (footprint "eagle-import:TP10R")
      (libsource (lib "eagle-import") (part "TPTP10R"))
    )
    (comp (ref "SWDIO1")
      (value "TPTP12R")
      (footprint "eagle-import:TP12R")
      (libsource (lib "eagle-import") (part "TPTP12R"))
    )
    (comp (ref "SWDIO2")
      (value "TPTP12R")
      (footprint "eagle-import:TP12R")
      (libsource (lib "eagle-import") (part "TPTP12R"))
    )
    (comp (ref "SWDIO3")
      (value "TPTP12R")
      (footprint "eagle-import:TP12R")
      (libsource (lib "eagle-import") (part "TPTP12R"))
    )
    (comp (ref "SWDIO4")
      (value "TPTP12R")
      (footprint "eagle-import:TP12R")
      (libsource (lib "eagle-import") (part "TPTP12R"))
    )
    (comp (ref "SWDIO5")
      (value "TPTP12R")
      (footprint "eagle-import:TP12R")
      (libsource (lib "eagle-import") (part "TPTP12R"))
    )
    (comp (ref "SWDIO6")
      (value "TPTP12R")
      (footprint "eagle-import:TP12R")
      (libsource (lib "eagle-import") (part "TPTP12R"))
    )
    (comp (ref "U15")
      (value "SKY13330-397LF")
      (footprint "eagle-import:QFN12")
      (libsource (lib "eagle-import") (part "SKYWORKS-13330397LF"))
    )
  )
  (nets
    (net (code "1") (name "3.3V") (class "Default")
      (node (ref "3V3") (pin "TP") (pinfunction "TP_TP") (pintype "input"))
      (node (ref "C1") (pin "P$1") (pinfunction "1_P$1") (pintype "passive"))
      (node (ref "C14") (pin "P$1") (pinfunction "1_P$1") (pintype "passive"))
      (node (ref "C15") (pin "P$1") (pinfunction "1_P$1") (pintype "passive"))
      (node (ref "C16") (pin "P$1") (pinfunction "1_P$1") (pintype "passive"))
      (node (ref "C17") (pin "P$1") (pinfunction "1_P$1") (pintype "passive"))
      (node (ref "C26") (pin "P$1") (pinfunction "1_P$1") (pintype "passive"))
      (node (ref "C28") (pin "P$1") (pinfunction "1_P$1") (pintype "passive"))
      (node (ref "C3") (pin "P$1") (pinfunction "1_P$1") (pintype "passive"))
      (node (ref "C32") (pin "P$1") (pinfunction "1_P$1") (pintype "passive"))
      (node (ref "C34") (pin "P$1") (pinfunction "1_P$1") (pintype "passive"))
      (node (ref "C46") (pin "P$1") (pinfunction "1_P$1") (pintype "passive"))
      (node (ref "C5") (pin "P$1") (pinfunction "1_P$1") (pintype "passive"))
      (node (ref "JLINK") (pin "5") (pinfunction "5_5") (pintype "passive"))
      (node (ref "L12") (pin "P$2") (pinfunction "2_P$2") (pintype "passive"))
      (node (ref "R1") (pin "P$2") (pinfunction "P$2_P$2") (pintype "passive"))
      (node (ref "R16") (pin "P$2") (pinfunction "P$2_P$2") (pintype "passive"))
      (node (ref "R20") (pin "P$2") (pinfunction "P$2_P$2") (pintype "passive"))
      (node (ref "R22") (pin "P$2") (pinfunction "P$2_P$2") (pintype "passive"))
      (node (ref "U1") (pin "1") (pinfunction "FB_1") (pintype "bidirectional"))
      (node (ref "U11") (pin "6") (pinfunction "VDD_1_6") (pintype "power_in"))
      (node (ref "U11") (pin "8") (pinfunction "VDD_2_8") (pintype "power_in"))
      (node (ref "U12") (pin "6") (pinfunction "VDD_1_6") (pintype "power_in"))
      (node (ref "U12") (pin "8") (pinfunction "VDD_2_8") (pintype "power_in"))
      (node (ref "U13") (pin "1") (pinfunction "VDD_1") (pintype "bidirectional"))
      (node (ref "U13") (pin "17") (pinfunction "VDD_17") (pintype "bidirectional"))
      (node (ref "U13") (pin "5") (pinfunction "VDDA_5") (pintype "bidirectional"))
      (node (ref "U15") (pin "P$9") (pinfunction "VCC_P$9") (pintype "bidirectional"))
      (node (ref "U2") (pin "P$6") (pinfunction "VBAT_P$6") (pintype "bidirectional"))
      (node (ref "U2") (pin "P$8") (pinfunction "VCC_P$8") (pintype "bidirectional"))
      (node (ref "U6") (pin "4") (pinfunction "VCC_4") (pintype "bidirectional"))
      (node (ref "U8") (pin "4") (pinfunction "S_4") (pintype "passive"))
    )
    (net (code "2") (name "BOOT0") (class "Default")
      (node (ref "BOOT0") (pin "TP") (pinfunction "TP_TP") (pintype "input"))
      (node (ref "R23") (pin "P$1") (pinfunction "P$1_P$1") (pintype "passive"))
      (node (ref "U13") (pin "31") (pinfunction "BOOT0_31") (pintype "bidirectional"))
    )
    (net (code "3") (name "CS1") (class "Default")
      (node (ref "U11") (pin "15") (pinfunction "NSEL_15") (pintype "input"))
      (node (ref "U13") (pin "10") (pinfunction "PA4_10") (pintype "bidirectional"))
    )
    (net (code "4") (name "CS2") (class "Default")
      (node (ref "U12") (pin "15") (pinfunction "NSEL_15") (pintype "input"))
      (node (ref "U13") (pin "6") (pinfunction "PA0_6") (pintype "bidirectional"))
    )
    (net (code "5") (name "GND") (class "Default")
      (node (ref "C1") (pin "P$2") (pinfunction "2_P$2") (pintype "passive"))
      (node (ref "C11") (pin "P$2") (pinfunction "2_P$2") (pintype "passive"))
      (node (ref "C13") (pin "P$2") (pinfunction "2_P$2") (pintype "passive"))
      (node (ref "C14") (pin "P$2") (pinfunction "2_P$2") (pintype "passive"))
      (node (ref "C15") (pin "P$2") (pinfunction "2_P$2") (pintype "passive"))
      (node (ref "C16") (pin "P$2") (pinfunction "2_P$2") (pintype "passive"))
      (node (ref "C17") (pin "P$2") (pinfunction "2_P$2") (pintype "passive"))
      (node (ref "C21") (pin "P$2") (pinfunction "2_P$2") (pintype "passive"))
      (node (ref "C23") (pin "P$2") (pinfunction "2_P$2") (pintype "passive"))
      (node (ref "C24") (pin "P$2") (pinfunction "2_P$2") (pintype "passive"))
      (node (ref "C25") (pin "P$2") (pinfunction "2_P$2") (pintype "passive"))
      (node (ref "C26") (pin "P$2") (pinfunction "2_P$2") (pintype "passive"))
      (node (ref "C28") (pin "P$2") (pinfunction "2_P$2") (pintype "passive"))
      (node (ref "C3") (pin "P$2") (pinfunction "2_P$2") (pintype "passive"))
      (node (ref "C30") (pin "P$2") (pinfunction "2_P$2") (pintype "passive"))
      (node (ref "C32") (pin "P$2") (pinfunction "2_P$2") (pintype "passive"))
      (node (ref "C34") (pin "P$2") (pinfunction "2_P$2") (pintype "passive"))
      (node (ref "C36") (pin "P$2") (pinfunction "2_P$2") (pintype "passive"))
      (node (ref "C37") (pin "P$2") (pinfunction "2_P$2") (pintype "passive"))
      (node (ref "C39") (pin "P$2") (pinfunction "2_P$2") (pintype "passive"))
      (node (ref "C4") (pin "P$2") (pinfunction "2_P$2") (pintype "passive"))
      (node (ref "C42") (pin "P$2") (pinfunction "2_P$2") (pintype "passive"))
      (node (ref "C43") (pin "P$2") (pinfunction "2_P$2") (pintype "passive"))
      (node (ref "C46") (pin "P$2") (pinfunction "2_P$2") (pintype "passive"))
      (node (ref "C47") (pin "P$2") (pinfunction "2_P$2") (pintype "passive"))
      (node (ref "C49") (pin "P$2") (pinfunction "2_P$2") (pintype "passive"))
      (node (ref "C5") (pin "P$2") (pinfunction "2_P$2") (pintype "passive"))
      (node (ref "C52") (pin "P$2") (pinfunction "2_P$2") (pintype "passive"))
      (node (ref "C53") (pin "P$2") (pinfunction "2_P$2") (pintype "passive"))
      (node (ref "C6") (pin "P$2") (pinfunction "2_P$2") (pintype "passive"))
      (node (ref "C7") (pin "P$2") (pinfunction "2_P$2") (pintype "passive"))
      (node (ref "C8") (pin "P$2") (pinfunction "2_P$2") (pintype "passive"))
      (node (ref "D1") (pin "A") (pinfunction "A_A") (pintype "passive"))
      (node (ref "D2") (pin "A") (pinfunction "A_A") (pintype "passive"))
      (node (ref "D3") (pin "C") (pinfunction "P$2_C") (pintype "bidirectional"))
      (node (ref "GND1") (pin "TP") (pinfunction "TP_TP") (pintype "input"))
      (node (ref "GND2") (pin "TP") (pinfunction "TP_TP") (pintype "input"))
      (node (ref "J$1") (pin "GND@0") (pinfunction "GND_GND@0") (pintype "bidirectional"))
      (node (ref "J$1") (pin "GND@1") (pinfunction "GND_GND@1") (pintype "bidirectional"))
      (node (ref "J$1") (pin "GND@2") (pinfunction "GND_GND@2") (pintype "bidirectional"))
      (node (ref "J$1") (pin "GND@3") (pinfunction "GND_GND@3") (pintype "bidirectional"))
      (node (ref "JLINK") (pin "1") (pinfunction "1_1") (pintype "passive"))
      (node (ref "JP1") (pin "8") (pinfunction "8_8") (pintype "bidirectional"))
      (node (ref "L14") (pin "P$1") (pinfunction "1_P$1") (pintype "passive"))
      (node (ref "Q1") (pin "1") (pinfunction "G_1") (pintype "passive"))
      (node (ref "R12") (pin "P$1") (pinfunction "P$1_P$1") (pintype "passive"))
      (node (ref "R18") (pin "P$1") (pinfunction "P$1_P$1") (pintype "passive"))
      (node (ref "R19") (pin "P$1") (pinfunction "P$1_P$1") (pintype "passive"))
      (node (ref "R23") (pin "P$2") (pinfunction "P$2_P$2") (pintype "passive"))
      (node (ref "R4") (pin "P$1") (pinfunction "P$1_P$1") (pintype "passive"))
      (node (ref "R7") (pin "P$2") (pinfunction "P$2_P$2") (pintype "passive"))
      (node (ref "R9") (pin "P$1") (pinfunction "P$1_P$1") (pintype "passive"))
      (node (ref "S1") (pin "P$2") (pinfunction "S2_P$2") (pintype "bidirectional"))
      (node (ref "SWDIO1") (pin "TP") (pinfunction "TP_TP") (pintype "input"))
      (node (ref "SWDIO2") (pin "TP") (pinfunction "TP_TP") (pintype "input"))
      (node (ref "SWDIO3") (pin "TP") (pinfunction "TP_TP") (pintype "input"))
      (node (ref "SWDIO4") (pin "TP") (pinfunction "TP_TP") (pintype "input"))
      (node (ref "SWDIO5") (pin "TP") (pinfunction "TP_TP") (pintype "input"))
      (node (ref "SWDIO6") (pin "TP") (pinfunction "TP_TP") (pintype "input"))
      (node (ref "U1") (pin "4") (pinfunction "GND_4") (pintype "bidirectional"))
      (node (ref "U11") (pin "18") (pinfunction "GNDX_18") (pintype "bidirectional"))
      (node (ref "U11") (pin "3") (pinfunction "RXN_3") (pintype "input"))
      (node (ref "U11") (pin "5") (pinfunction "NC_5") (pintype "bidirectional"))
      (node (ref "U11") (pin "EXP") (pinfunction "PAD_EXP") (pintype "bidirectional"))
      (node (ref "U12") (pin "18") (pinfunction "GNDX_18") (pintype "bidirectional"))
      (node (ref "U12") (pin "3") (pinfunction "RXN_3") (pintype "input"))
      (node (ref "U12") (pin "5") (pinfunction "NC_5") (pintype "bidirectional"))
      (node (ref "U12") (pin "EXP") (pinfunction "PAD_EXP") (pintype "bidirectional"))
      (node (ref "U13") (pin "16") (pinfunction "VSS_16") (pintype "bidirectional"))
      (node (ref "U13") (pin "32") (pinfunction "VSS_32") (pintype "bidirectional"))
      (node (ref "U13") (pin "EXP") (pinfunction "PAD_EXP") (pintype "bidirectional"))
      (node (ref "U14") (pin "1") (pinfunction "S_1") (pintype "bidirectional"))
      (node (ref "U14") (pin "4") (pinfunction "S_4") (pintype "bidirectional"))
      (node (ref "U15") (pin "P$1") (pinfunction "GND_P$1") (pintype "bidirectional"))
      (node (ref "U15") (pin "P$10") (pinfunction "GND_P$10") (pintype "bidirectional"))
      (node (ref "U15") (pin "P$12") (pinfunction "GND_P$12") (pintype "bidirectional"))
      (node (ref "U15") (pin "P$13") (pinfunction "GND_P$13") (pintype "bidirectional"))
      (node (ref "U15") (pin "P$3") (pinfunction "GND_P$3") (pintype "bidirectional"))
      (node (ref "U15") (pin "P$4") (pinfunction "GND_P$4") (pintype "bidirectional"))
      (node (ref "U15") (pin "P$6") (pinfunction "GND_P$6") (pintype "bidirectional"))
      (node (ref "U17") (pin "1") (pinfunction "S_1") (pintype "bidirectional"))
      (node (ref "U17") (pin "4") (pinfunction "S_4") (pintype "bidirectional"))
      (node (ref "U2") (pin "P$1") (pinfunction "GND_P$1") (pintype "bidirectional"))
      (node (ref "U2") (pin "P$10") (pinfunction "GND_P$10") (pintype "bidirectional"))
      (node (ref "U2") (pin "P$12") (pinfunction "GND_P$12") (pintype "bidirectional"))
      (node (ref "U3") (pin "P$4") (pinfunction "GND_P$4") (pintype "bidirectional"))
      (node (ref "U3") (pin "P$7") (pinfunction "GND_P$7") (pintype "bidirectional"))
      (node (ref "U4") (pin "4") (pinfunction "S_4") (pintype "bidirectional"))
      (node (ref "U5") (pin "2") (pinfunction "GND_2") (pintype "bidirectional"))
      (node (ref "U5") (pin "4") (pinfunction "GND_4") (pintype "bidirectional"))
      (node (ref "U5") (pin "5") (pinfunction "GND_5") (pintype "bidirectional"))
      (node (ref "U6") (pin "2") (pinfunction "GND_2") (pintype "bidirectional"))
      (node (ref "U6") (pin "5") (pinfunction "WP_5") (pintype "bidirectional"))
      (node (ref "U7") (pin "2") (pinfunction "S_2") (pintype "passive"))
      (node (ref "U7") (pin "2@1") (pinfunction "PAD_2@1") (pintype "bidirectional"))
      (node (ref "U8") (pin "1") (pinfunction "S_1") (pintype "bidirectional"))
      (node (ref "U9") (pin "P$3") (pinfunction "GND_P$3") (pintype "bidirectional"))
      (node (ref "X1") (pin "2") (pinfunction "G2_2") (pintype "power_in"))
      (node (ref "X1") (pin "4") (pinfunction "G1_4") (pintype "power_in"))
      (node (ref "X2") (pin "2") (pinfunction "G2_2") (pintype "power_in"))
      (node (ref "X2") (pin "4") (pinfunction "G1_4") (pintype "power_in"))
    )
    (net (code "6") (name "GPS_1PPS") (class "Default")
      (node (ref "U2") (pin "P$4") (pinfunction "1PPS_P$4") (pintype "bidirectional"))
      (node (ref "U4") (pin "5") (pinfunction "G_5") (pintype "bidirectional"))
    )
    (net (code "7") (name "GPS_EN") (class "Default")
      (node (ref "R3") (pin "P$2") (pinfunction "P$2_P$2") (pintype "passive"))
      (node (ref "R6") (pin "P$2") (pinfunction "P$2_P$2") (pintype "passive"))
      (node (ref "R7") (pin "P$1") (pinfunction "P$1_P$1") (pintype "passive"))
      (node (ref "U13") (pin "2") (pinfunction "OSC_IN/PC14_2") (pintype "bidirectional"))
      (node (ref "U4") (pin "2") (pinfunction "G_2") (pintype "bidirectional"))
    )
    (net (code "8") (name "GPS_STATUS") (class "Default")
      (node (ref "U13") (pin "21") (pinfunction "PA11_21") (pintype "bidirectional"))
      (node (ref "U14") (pin "5") (pinfunction "G_5") (pintype "bidirectional"))
    )
    (net (code "9") (name "GPS_UART_TX") (class "Default")
      (node (ref "R3") (pin "P$1") (pinfunction "P$1_P$1") (pintype "passive"))
      (node (ref "U2") (pin "P$2") (pinfunction "TX_P$2") (pintype "bidirectional"))
      (node (ref "U4") (pin "1") (pinfunction "S_1") (pintype "bidirectional"))
    )
    (net (code "10") (name "HOST_GPS_STATUS") (class "Default")
      (node (ref "JP1") (pin "4") (pinfunction "4_4") (pintype "bidirectional"))
      (node (ref "R14") (pin "P$2") (pinfunction "P$2_P$2") (pintype "passive"))
      (node (ref "U9") (pin "P$2") (pinfunction "C2_P$2") (pintype "bidirectional"))
    )
    (net (code "11") (name "HOST_RX_STATUS") (class "Default")
      (node (ref "JP1") (pin "6") (pinfunction "6_6") (pintype "bidirectional"))
      (node (ref "R15") (pin "P$2") (pinfunction "P$2_P$2") (pintype "passive"))
      (node (ref "U9") (pin "P$7") (pinfunction "C6_P$7") (pintype "bidirectional"))
    )
    (net (code "12") (name "HOST_TX_OFF") (class "Default")
      (node (ref "JP1") (pin "2") (pinfunction "2_2") (pintype "bidirectional"))
      (node (ref "R18") (pin "P$2") (pinfunction "P$2_P$2") (pintype "passive"))
      (node (ref "U17") (pin "2") (pinfunction "G_2") (pintype "bidirectional"))
      (node (ref "U9") (pin "P$1") (pinfunction "C1_P$1") (pintype "bidirectional"))
    )
    (net (code "13") (name "HOST_TX_STATUS") (class "Default")
      (node (ref "JP1") (pin "7") (pinfunction "7_7") (pintype "bidirectional"))
      (node (ref "R17") (pin "P$2") (pinfunction "P$2_P$2") (pintype "passive"))
      (node (ref "U9") (pin "P$6") (pinfunction "C5_P$6") (pintype "bidirectional"))
    )
    (net (code "14") (name "HOST_UART_RX") (class "Default")
      (node (ref "JP1") (pin "5") (pinfunction "5_5") (pintype "bidirectional"))
      (node (ref "R13") (pin "P$2") (pinfunction "P$2_P$2") (pintype "passive"))
      (node (ref "U9") (pin "P$8") (pinfunction "C7_P$8") (pintype "bidirectional"))
    )
    (net (code "15") (name "HOST_UART_TX") (class "Default")
      (node (ref "JP1") (pin "3") (pinfunction "3_3") (pintype "bidirectional"))
      (node (ref "R2") (pin "P$2") (pinfunction "P$2_P$2") (pintype "passive"))
      (node (ref "U9") (pin "P$9") (pinfunction "C8_P$9") (pintype "bidirectional"))
    )
    (net (code "16") (name "I2C_SCL") (class "Default")
      (node (ref "SCL") (pin "TP") (pinfunction "TP_TP") (pintype "input"))
      (node (ref "U13") (pin "29") (pinfunction "PB6_29") (pintype "bidirectional"))
      (node (ref "U6") (pin "1") (pinfunction "SCL_1") (pintype "bidirectional"))
    )
    (net (code "17") (name "I2C_SDA") (class "Default")
      (node (ref "SDA") (pin "TP") (pinfunction "TP_TP") (pintype "input"))
      (node (ref "U13") (pin "30") (pinfunction "PB7_30") (pintype "bidirectional"))
      (node (ref "U6") (pin "3") (pinfunction "SDA_3") (pintype "bidirectional"))
    )
    (net (code "18") (name "MCU_GPS_1PPS") (class "Default")
      (node (ref "R6") (pin "P$1") (pinfunction "P$1_P$1") (pintype "passive"))
      (node (ref "U13") (pin "8") (pinfunction "PA2_8") (pintype "bidirectional"))
      (node (ref "U4") (pin "3") (pinfunction "D_3") (pintype "bidirectional"))
    )
    (net (code "19") (name "MCU_GPS_UART_RX") (class "Default")
      (node (ref "R16") (pin "P$1") (pinfunction "P$1_P$1") (pintype "passive"))
      (node (ref "U13") (pin "9") (pinfunction "PA3_9") (pintype "bidirectional"))
      (node (ref "U4") (pin "6") (pinfunction "D_6") (pintype "bidirectional"))
    )
    (net (code "20") (name "MCU_TX_OFF") (class "Default")
      (node (ref "U13") (pin "22") (pinfunction "PA12_22") (pintype "bidirectional"))
      (node (ref "U17") (pin "6") (pinfunction "D_6") (pintype "bidirectional"))
    )
    (net (code "21") (name "MCU_UART_RX") (class "Default")
      (node (ref "D1") (pin "C") (pinfunction "C_C") (pintype "passive"))
      (node (ref "R2") (pin "P$1") (pinfunction "P$1_P$1") (pintype "passive"))
      (node (ref "RX") (pin "TP") (pinfunction "TP_TP") (pintype "input"))
      (node (ref "U13") (pin "20") (pinfunction "PA10_20") (pintype "bidirectional"))
    )
    (net (code "22") (name "MCU_UART_TX") (class "Default")
      (node (ref "D2") (pin "C") (pinfunction "C_C") (pintype "passive"))
      (node (ref "R13") (pin "P$1") (pinfunction "P$1_P$1") (pintype "passive"))
      (node (ref "TX") (pin "TP") (pinfunction "TP_TP") (pintype "input"))
      (node (ref "U13") (pin "19") (pinfunction "PA9_19") (pintype "bidirectional"))
    )
    (net (code "23") (name "MISO") (class "Default")
      (node (ref "U11") (pin "13") (pinfunction "SDO_13") (pintype "output"))
      (node (ref "U12") (pin "13") (pinfunction "SDO_13") (pintype "output"))
      (node (ref "U13") (pin "12") (pinfunction "PA6_12") (pintype "bidirectional"))
    )
    (net (code "24") (name "MOSI") (class "Default")
      (node (ref "U11") (pin "14") (pinfunction "SDI_14") (pintype "input"))
      (node (ref "U12") (pin "14") (pinfunction "SDI_14") (pintype "input"))
      (node (ref "U13") (pin "13") (pinfunction "PA7_13") (pintype "bidirectional"))
    )
    (net (code "25") (name "NRST") (class "Default")
      (node (ref "JLINK") (pin "2") (pinfunction "2_2") (pintype "passive"))
      (node (ref "NRST") (pin "TP") (pinfunction "TP_TP") (pintype "input"))
      (node (ref "S1") (pin "P$1") (pinfunction "S1_P$1") (pintype "bidirectional"))
      (node (ref "U13") (pin "4") (pinfunction "NRST_4") (pintype "bidirectional"))
    )
    (net (code "26") (name "Net-(C2-1)") (class "Default")
      (node (ref "C2") (pin "P$1") (pinfunction "1_P$1") (pintype "passive"))
      (node (ref "U1") (pin "6") (pinfunction "BST_6") (pintype "bidirectional"))
    )
    (net (code "27") (name "Net-(C2-2)") (class "Default")
      (node (ref "C2") (pin "P$2") (pinfunction "2_P$2") (pintype "passive"))
      (node (ref "L12") (pin "P$1") (pinfunction "1_P$1") (pintype "passive"))
      (node (ref "U1") (pin "5") (pinfunction "SW_5") (pintype "bidirectional"))
    )
    (net (code "28") (name "Net-(C9-1)") (class "Default")
      (node (ref "C9") (pin "P$1") (pinfunction "1_P$1") (pintype "passive"))
      (node (ref "L8") (pin "P$2") (pinfunction "2_P$2") (pintype "passive"))
    )
    (net (code "29") (name "Net-(C10-1)") (class "Default")
      (node (ref "C10") (pin "P$1") (pinfunction "1_P$1") (pintype "passive"))
      (node (ref "C8") (pin "P$1") (pinfunction "1_P$1") (pintype "passive"))
      (node (ref "C9") (pin "P$2") (pinfunction "2_P$2") (pintype "passive"))
      (node (ref "L14") (pin "P$2") (pinfunction "2_P$2") (pintype "passive"))
    )
    (net (code "30") (name "Net-(C10-2)") (class "Default")
      (node (ref "C10") (pin "P$2") (pinfunction "2_P$2") (pintype "passive"))
      (node (ref "L13") (pin "P$1") (pinfunction "1_P$1") (pintype "passive"))
    )
    (net (code "31") (name "Net-(C12-1)") (class "Default")
      (node (ref "C12") (pin "P$1") (pinfunction "1_P$1") (pintype "passive"))
      (node (ref "L13") (pin "P$2") (pinfunction "2_P$2") (pintype "passive"))
    )
    (net (code "32") (name "Net-(C12-2)") (class "Default")
      (node (ref "C12") (pin "P$2") (pinfunction "2_P$2") (pintype "passive"))
      (node (ref "U5") (pin "6") (pinfunction "IN_6") (pintype "bidirectional"))
    )
    (net (code "33") (name "Net-(C13-1)") (class "Default")
      (node (ref "C13") (pin "P$1") (pinfunction "1_P$1") (pintype "passive"))
      (node (ref "R10") (pin "P$2") (pinfunction "P$2_P$2") (pintype "passive"))
      (node (ref "U5") (pin "1") (pinfunction "VCC_1") (pintype "bidirectional"))
    )
    (net (code "34") (name "Net-(C18-1)") (class "Default")
      (node (ref "C18") (pin "P$1") (pinfunction "1_P$1") (pintype "passive"))
      (node (ref "U5") (pin "3") (pinfunction "OUT_3") (pintype "bidirectional"))
    )
    (net (code "35") (name "Net-(C21-1)") (class "Default")
      (node (ref "C21") (pin "P$1") (pinfunction "1_P$1") (pintype "passive"))
      (node (ref "L5") (pin "P$1") (pinfunction "1_P$1") (pintype "passive"))
      (node (ref "R22") (pin "P$1") (pinfunction "P$1_P$1") (pintype "passive"))
    )
    (net (code "36") (name "Net-(C22-1)") (class "Default")
      (node (ref "C22") (pin "P$1") (pinfunction "1_P$1") (pintype "passive"))
      (node (ref "L5") (pin "P$2") (pinfunction "2_P$2") (pintype "passive"))
      (node (ref "U11") (pin "4") (pinfunction "TX_4") (pintype "output"))
    )
    (net (code "37") (name "Net-(C22-2)") (class "Default")
      (node (ref "C22") (pin "P$2") (pinfunction "2_P$2") (pintype "passive"))
      (node (ref "L1") (pin "P$1") (pinfunction "1_P$1") (pintype "passive"))
    )
    (net (code "38") (name "Net-(C23-1)") (class "Default")
      (node (ref "C23") (pin "P$1") (pinfunction "1_P$1") (pintype "passive"))
      (node (ref "L1") (pin "P$2") (pinfunction "2_P$2") (pintype "passive"))
      (node (ref "L6") (pin "P$1") (pinfunction "1_P$1") (pintype "passive"))
    )
    (net (code "39") (name "Net-(C24-1)") (class "Default")
      (node (ref "C24") (pin "P$1") (pinfunction "1_P$1") (pintype "passive"))
      (node (ref "L6") (pin "P$2") (pinfunction "2_P$2") (pintype "passive"))
      (node (ref "L7") (pin "P$1") (pinfunction "1_P$1") (pintype "passive"))
    )
    (net (code "40") (name "Net-(C25-1)") (class "Default")
      (node (ref "C25") (pin "P$1") (pinfunction "1_P$1") (pintype "passive"))
      (node (ref "L11") (pin "P$1") (pinfunction "1_P$1") (pintype "passive"))
      (node (ref "L7") (pin "P$2") (pinfunction "2_P$2") (pintype "passive"))
    )
    (net (code "41") (name "Net-(C29-2)") (class "Default")
      (node (ref "C29") (pin "P$2") (pinfunction "2_P$2") (pintype "passive"))
      (node (ref "C30") (pin "P$1") (pinfunction "1_P$1") (pintype "passive"))
      (node (ref "L3") (pin "P$1") (pinfunction "1_P$1") (pintype "passive"))
    )
    (net (code "42") (name "Net-(C36-1)") (class "Default")
      (node (ref "C36") (pin "P$1") (pinfunction "1_P$1") (pintype "passive"))
      (node (ref "L10") (pin "P$1") (pinfunction "1_P$1") (pintype "passive"))
      (node (ref "L9") (pin "P$2") (pinfunction "2_P$2") (pintype "passive"))
    )
    (net (code "43") (name "Net-(C37-1)") (class "Default")
      (node (ref "C37") (pin "P$1") (pinfunction "1_P$1") (pintype "passive"))
      (node (ref "C39") (pin "P$1") (pinfunction "1_P$1") (pintype "passive"))
      (node (ref "L4") (pin "P$2") (pinfunction "2_P$2") (pintype "passive"))
      (node (ref "L9") (pin "P$1") (pinfunction "1_P$1") (pintype "passive"))
      (node (ref "U7") (pin "3") (pinfunction "D_3") (pintype "passive"))
    )
    (net (code "44") (name "Net-(C42-1)") (class "Default")
      (node (ref "C42") (pin "P$1") (pinfunction "1_P$1") (pintype "passive"))
      (node (ref "C52") (pin "P$1") (pinfunction "1_P$1") (pintype "passive"))
      (node (ref "L10") (pin "P$2") (pinfunction "2_P$2") (pintype "passive"))
      (node (ref "L23") (pin "P$1") (pinfunction "1_P$1") (pintype "passive"))
    )
    (net (code "45") (name "Net-(C43-1)") (class "Default")
      (node (ref "C43") (pin "P$1") (pinfunction "1_P$1") (pintype "passive"))
      (node (ref "C6") (pin "P$1") (pinfunction "1_P$1") (pintype "passive"))
      (node (ref "L2") (pin "P$2") (pinfunction "2_P$2") (pintype "passive"))
      (node (ref "U1") (pin "2") (pinfunction "EN_2") (pintype "bidirectional"))
      (node (ref "U1") (pin "3") (pinfunction "VIN_3") (pintype "bidirectional"))
    )
    (net (code "46") (name "Net-(C44-1)") (class "Default")
      (node (ref "C44") (pin "P$1") (pinfunction "1_P$1") (pintype "passive"))
      (node (ref "C53") (pin "P$1") (pinfunction "1_P$1") (pintype "passive"))
      (node (ref "L23") (pin "P$2") (pinfunction "2_P$2") (pintype "passive"))
    )
    (net (code "47") (name "Net-(J$1-SIGNAL)") (class "Default")
      (node (ref "J$1") (pin "SIG") (pinfunction "SIGNAL_SIG") (pintype "bidirectional"))
      (node (ref "RF") (pin "TP") (pinfunction "TP_TP") (pintype "input"))
      (node (ref "U15") (pin "P$2") (pinfunction "RF1_P$2") (pintype "bidirectional"))
    )
    (net (code "48") (name "Net-(L17-1)") (class "Default")
      (node (ref "L17") (pin "P$1") (pinfunction "1_P$1") (pintype "passive"))
      (node (ref "L3") (pin "P$2") (pinfunction "2_P$2") (pintype "passive"))
      (node (ref "U7") (pin "1") (pinfunction "G_1") (pintype "passive"))
    )
    (net (code "49") (name "Net-(Q1-D)") (class "Default")
      (node (ref "F1") (pin "2") (pinfunction "2_2") (pintype "bidirectional"))
      (node (ref "Q1") (pin "3") (pinfunction "D_3") (pintype "passive"))
    )
    (net (code "50") (name "Net-(U3-ADJ)") (class "Default")
      (node (ref "R4") (pin "P$2") (pinfunction "P$2_P$2") (pintype "passive"))
      (node (ref "R5") (pin "P$1") (pinfunction "P$1_P$1") (pintype "passive"))
      (node (ref "U3") (pin "P$2") (pinfunction "ADJ_P$2") (pintype "bidirectional"))
    )
    (net (code "51") (name "Net-(U8A-D)") (class "Default")
      (node (ref "R1") (pin "P$1") (pinfunction "P$1_P$1") (pintype "passive"))
      (node (ref "U8") (pin "5") (pinfunction "G_5") (pintype "passive"))
      (node (ref "U8") (pin "6") (pinfunction "D_6") (pintype "bidirectional"))
    )
    (net (code "52") (name "Net-(U10-RF)") (class "Default")
      (node (ref "U10") (pin "P$1") (pinfunction "RF_P$1") (pintype "bidirectional"))
      (node (ref "U2") (pin "P$11") (pinfunction "RFIN_P$11") (pintype "bidirectional"))
    )
    (net (code "53") (name "Net-(U11-XIN)") (class "Default")
      (node (ref "U11") (pin "17") (pinfunction "XIN_17") (pintype "input"))
      (node (ref "X1") (pin "3") (pinfunction "X2_3") (pintype "bidirectional"))
    )
    (net (code "54") (name "Net-(U11-XOUT)") (class "Default")
      (node (ref "U11") (pin "16") (pinfunction "XOUT_16") (pintype "bidirectional"))
      (node (ref "X1") (pin "1") (pinfunction "X1_1") (pintype "bidirectional"))
    )
    (net (code "55") (name "Net-(U12-XIN)") (class "Default")
      (node (ref "U12") (pin "17") (pinfunction "XIN_17") (pintype "input"))
      (node (ref "X2") (pin "3") (pinfunction "X2_3") (pintype "bidirectional"))
    )
    (net (code "56") (name "Net-(U12-XOUT)") (class "Default")
      (node (ref "U12") (pin "16") (pinfunction "XOUT_16") (pintype "bidirectional"))
      (node (ref "X2") (pin "1") (pinfunction "X1_1") (pintype "bidirectional"))
    )
    (net (code "57") (name "Net-(U14A-D)") (class "Default")
      (node (ref "R14") (pin "P$1") (pinfunction "P$1_P$1") (pintype "passive"))
      (node (ref "U14") (pin "3") (pinfunction "D_3") (pintype "bidirectional"))
    )
    (net (code "58") (name "Net-(U14B-D)") (class "Default")
      (node (ref "R15") (pin "P$1") (pinfunction "P$1_P$1") (pintype "passive"))
      (node (ref "U14") (pin "6") (pinfunction "D_6") (pintype "bidirectional"))
    )
    (net (code "59") (name "Net-(U15-CTRL)") (class "Default")
      (node (ref "R8") (pin "P$1") (pinfunction "P$1_P$1") (pintype "passive"))
      (node (ref "R9") (pin "P$2") (pinfunction "P$2_P$2") (pintype "passive"))
      (node (ref "U15") (pin "P$7") (pinfunction "CTRL_P$7") (pintype "bidirectional"))
    )
    (net (code "60") (name "Net-(U17A-D)") (class "Default")
      (node (ref "R17") (pin "P$1") (pinfunction "P$1_P$1") (pintype "passive"))
      (node (ref "U17") (pin "3") (pinfunction "D_3") (pintype "bidirectional"))
    )
    (net (code "61") (name "PA_GATE_BIAS") (class "Default")
      (node (ref "C11") (pin "P$1") (pinfunction "1_P$1") (pintype "passive"))
      (node (ref "L17") (pin "P$2") (pinfunction "2_P$2") (pintype "passive"))
      (node (ref "R11") (pin "P$1") (pinfunction "P$1_P$1") (pintype "passive"))
      (node (ref "R12") (pin "P$2") (pinfunction "P$2_P$2") (pintype "passive"))
    )
    (net (code "62") (name "PA_IN") (class "Default")
      (node (ref "C29") (pin "P$1") (pinfunction "1_P$1") (pintype "passive"))
      (node (ref "L11") (pin "P$2") (pinfunction "2_P$2") (pintype "passive"))
    )
    (net (code "63") (name "PA_OUT") (class "Default")
      (node (ref "C44") (pin "P$2") (pinfunction "2_P$2") (pintype "passive"))
      (node (ref "U15") (pin "P$5") (pinfunction "RF3_P$5") (pintype "bidirectional"))
    )
    (net (code "64") (name "RFSW_EN") (class "Default")
      (node (ref "R19") (pin "P$2") (pinfunction "P$2_P$2") (pintype "passive"))
      (node (ref "R20") (pin "P$1") (pinfunction "P$1_P$1") (pintype "passive"))
      (node (ref "U15") (pin "P$8") (pinfunction "EN_P$8") (pintype "bidirectional"))
    )
    (net (code "65") (name "RF_IN") (class "Default")
      (node (ref "L8") (pin "P$1") (pinfunction "1_P$1") (pintype "passive"))
      (node (ref "U15") (pin "P$11") (pinfunction "RF2_P$11") (pintype "bidirectional"))
    )
    (net (code "66") (name "RX_EN") (class "Default")
      (node (ref "R8") (pin "P$2") (pinfunction "P$2_P$2") (pintype "passive"))
      (node (ref "U11") (pin "20") (pinfunction "GPIO3_20") (pintype "bidirectional"))
      (node (ref "U8") (pin "2") (pinfunction "G_2") (pintype "bidirectional"))
    )
    (net (code "67") (name "RX_IC_CLK") (class "Default")
      (node (ref "U12") (pin "20") (pinfunction "GPIO3_20") (pintype "bidirectional"))
      (node (ref "U13") (pin "26") (pinfunction "PB3_26") (pintype "bidirectional"))
    )
    (net (code "68") (name "RX_IC_DATA") (class "Default")
      (node (ref "U12") (pin "10") (pinfunction "GPIO1_10") (pintype "bidirectional"))
      (node (ref "U13") (pin "27") (pinfunction "PB4_27") (pintype "bidirectional"))
    )
    (net (code "69") (name "RX_IN") (class "Default")
      (node (ref "C18") (pin "P$2") (pinfunction "2_P$2") (pintype "passive"))
      (node (ref "U11") (pin "2") (pinfunction "RXP_2") (pintype "input"))
      (node (ref "U12") (pin "2") (pinfunction "RXP_2") (pintype "input"))
    )
    (net (code "70") (name "RX_STATUS") (class "Default")
      (node (ref "U13") (pin "7") (pinfunction "PA1_7") (pintype "bidirectional"))
      (node (ref "U14") (pin "2") (pinfunction "G_2") (pintype "bidirectional"))
    )
    (net (code "71") (name "SCK") (class "Default")
      (node (ref "U11") (pin "12") (pinfunction "SCLK_12") (pintype "input"))
      (node (ref "U12") (pin "12") (pinfunction "SCLK_12") (pintype "input"))
      (node (ref "U13") (pin "11") (pinfunction "PA5_11") (pintype "bidirectional"))
    )
    (net (code "72") (name "SDN1") (class "Default")
      (node (ref "U11") (pin "1") (pinfunction "SDN_1") (pintype "input"))
      (node (ref "U13") (pin "14") (pinfunction "PB0_14") (pintype "bidirectional"))
    )
    (net (code "73") (name "SDN2") (class "Default")
      (node (ref "U12") (pin "1") (pinfunction "SDN_1") (pintype "input"))
      (node (ref "U13") (pin "25") (pinfunction "PA15_25") (pintype "bidirectional"))
    )
    (net (code "74") (name "SWCLK") (class "Default")
      (node (ref "JLINK") (pin "3") (pinfunction "3_3") (pintype "passive"))
      (node (ref "SWCLK") (pin "TP") (pinfunction "TP_TP") (pintype "input"))
      (node (ref "U13") (pin "24") (pinfunction "PA14_24") (pintype "bidirectional"))
    )
    (net (code "75") (name "SWDIO") (class "Default")
      (node (ref "JLINK") (pin "4") (pinfunction "4_4") (pintype "passive"))
      (node (ref "SWDIO") (pin "TP") (pinfunction "TP_TP") (pintype "input"))
      (node (ref "U13") (pin "23") (pinfunction "PA13_23") (pintype "bidirectional"))
    )
    (net (code "76") (name "TRX_IC_CLOCK") (class "Default")
      (node (ref "U11") (pin "19") (pinfunction "GPIO2_19") (pintype "bidirectional"))
      (node (ref "U13") (pin "3") (pinfunction "OSC_OUT/PC15_3") (pintype "bidirectional"))
    )
    (net (code "77") (name "TRX_IC_DATA") (class "Default")
      (node (ref "U11") (pin "10") (pinfunction "GPIO1_10") (pintype "bidirectional"))
      (node (ref "U13") (pin "15") (pinfunction "PB1_15") (pintype "bidirectional"))
    )
    (net (code "78") (name "TX_STATUS") (class "Default")
      (node (ref "U13") (pin "28") (pinfunction "PB5_28") (pintype "bidirectional"))
      (node (ref "U17") (pin "5") (pinfunction "G_5") (pintype "bidirectional"))
    )
    (net (code "79") (name "V_IN") (class "Default")
      (node (ref "D3") (pin "A") (pinfunction "P$1_A") (pintype "bidirectional"))
      (node (ref "F1") (pin "1") (pinfunction "1_1") (pintype "bidirectional"))
      (node (ref "JP1") (pin "1") (pinfunction "1_1") (pintype "bidirectional"))
      (node (ref "V_IN") (pin "TP") (pinfunction "TP_TP") (pintype "input"))
    )
    (net (code "80") (name "V_LNA") (class "Default")
      (node (ref "R10") (pin "P$1") (pinfunction "P$1_P$1") (pintype "passive"))
      (node (ref "U8") (pin "3") (pinfunction "D_3") (pintype "passive"))
      (node (ref "V_LNA") (pin "TP") (pinfunction "TP_TP") (pintype "input"))
    )
    (net (code "81") (name "V_PA") (class "Default")
      (node (ref "C49") (pin "P$1") (pinfunction "1_P$1") (pintype "passive"))
      (node (ref "C7") (pin "P$1") (pinfunction "1_P$1") (pintype "passive"))
      (node (ref "L4") (pin "P$1") (pinfunction "1_P$1") (pintype "passive"))
      (node (ref "R5") (pin "P$2") (pinfunction "P$2_P$2") (pintype "passive"))
      (node (ref "U3") (pin "P$1") (pinfunction "VOUT_P$1") (pintype "bidirectional"))
      (node (ref "V_PA") (pin "TP") (pinfunction "TP_TP") (pintype "input"))
    )
    (net (code "82") (name "V_PA_BIAS") (class "Default")
      (node (ref "R11") (pin "P$2") (pinfunction "P$2_P$2") (pintype "passive"))
      (node (ref "U13") (pin "18") (pinfunction "PA8_18") (pintype "bidirectional"))
    )
    (net (code "83") (name "V_PROT") (class "Default")
      (node (ref "C4") (pin "P$1") (pinfunction "1_P$1") (pintype "passive"))
      (node (ref "C47") (pin "P$1") (pinfunction "1_P$1") (pintype "passive"))
      (node (ref "L2") (pin "P$1") (pinfunction "1_P$1") (pintype "passive"))
      (node (ref "Q1") (pin "2") (pinfunction "S_2") (pintype "passive"))
      (node (ref "U3") (pin "P$5") (pinfunction "EN_P$5") (pintype "bidirectional"))
      (node (ref "U3") (pin "P$6") (pinfunction "VIN_P$6") (pintype "bidirectional"))
    )
    (net (code "84") (name "unconnected-(S1-S1-PadP$4)") (class "Default")
      (node (ref "S1") (pin "P$4") (pinfunction "S1_P$4") (pintype "bidirectional"))
    )
    (net (code "85") (name "unconnected-(S1-S2-PadP$3)") (class "Default")
      (node (ref "S1") (pin "P$3") (pinfunction "S2_P$3") (pintype "bidirectional"))
    )
    (net (code "86") (name "unconnected-(U2-RX-PadP$3)") (class "Default")
      (node (ref "U2") (pin "P$3") (pinfunction "RX_P$3") (pintype "bidirectional"))
    )
    (net (code "87") (name "unconnected-(U3-PG-PadP$3)") (class "Default")
      (node (ref "U3") (pin "P$3") (pinfunction "PG_P$3") (pintype "bidirectional"))
    )
    (net (code "88") (name "unconnected-(U9-C3-PadP$4)") (class "Default")
      (node (ref "U9") (pin "P$4") (pinfunction "C3_P$4") (pintype "bidirectional"))
    )
    (net (code "89") (name "unconnected-(U9-C4-PadP$5)") (class "Default")
      (node (ref "U9") (pin "P$5") (pinfunction "C4_P$5") (pintype "bidirectional"))
    )
    (net (code "90") (name "unconnected-(U10-PAD-PadP$2)") (class "Default")
      (node (ref "U10") (pin "P$2") (pinfunction "PAD_P$2") (pintype "bidirectional"))
    )
    (net (code "91") (name "unconnected-(U11-GPIO0-Pad9)") (class "Default")
      (node (ref "U11") (pin "9") (pinfunction "GPIO0_9") (pintype "bidirectional"))
    )
    (net (code "92") (name "unconnected-(U11-NIRQ-Pad11)") (class "Default")
      (node (ref "U11") (pin "11") (pinfunction "NIRQ_11") (pintype "bidirectional"))
    )
    (net (code "93") (name "unconnected-(U11-TXRAMP-Pad7)") (class "Default")
      (node (ref "U11") (pin "7") (pinfunction "TXRAMP_7") (pintype "bidirectional"))
    )
    (net (code "94") (name "unconnected-(U12-GPIO0-Pad9)") (class "Default")
      (node (ref "U12") (pin "9") (pinfunction "GPIO0_9") (pintype "bidirectional"))
    )
    (net (code "95") (name "unconnected-(U12-GPIO2-Pad19)") (class "Default")
      (node (ref "U12") (pin "19") (pinfunction "GPIO2_19") (pintype "bidirectional"))
    )
    (net (code "96") (name "unconnected-(U12-NIRQ-Pad11)") (class "Default")
      (node (ref "U12") (pin "11") (pinfunction "NIRQ_11") (pintype "bidirectional"))
    )
    (net (code "97") (name "unconnected-(U12-TX-Pad4)") (class "Default")
      (node (ref "U12") (pin "4") (pinfunction "TX_4") (pintype "output"))
    )
    (net (code "98") (name "unconnected-(U12-TXRAMP-Pad7)") (class "Default")
      (node (ref "U12") (pin "7") (pinfunction "TXRAMP_7") (pintype "bidirectional"))
    )
  )
)
